# USB-PD-PSU.net
KiCad netlist of a schematic drawn in EAGLE
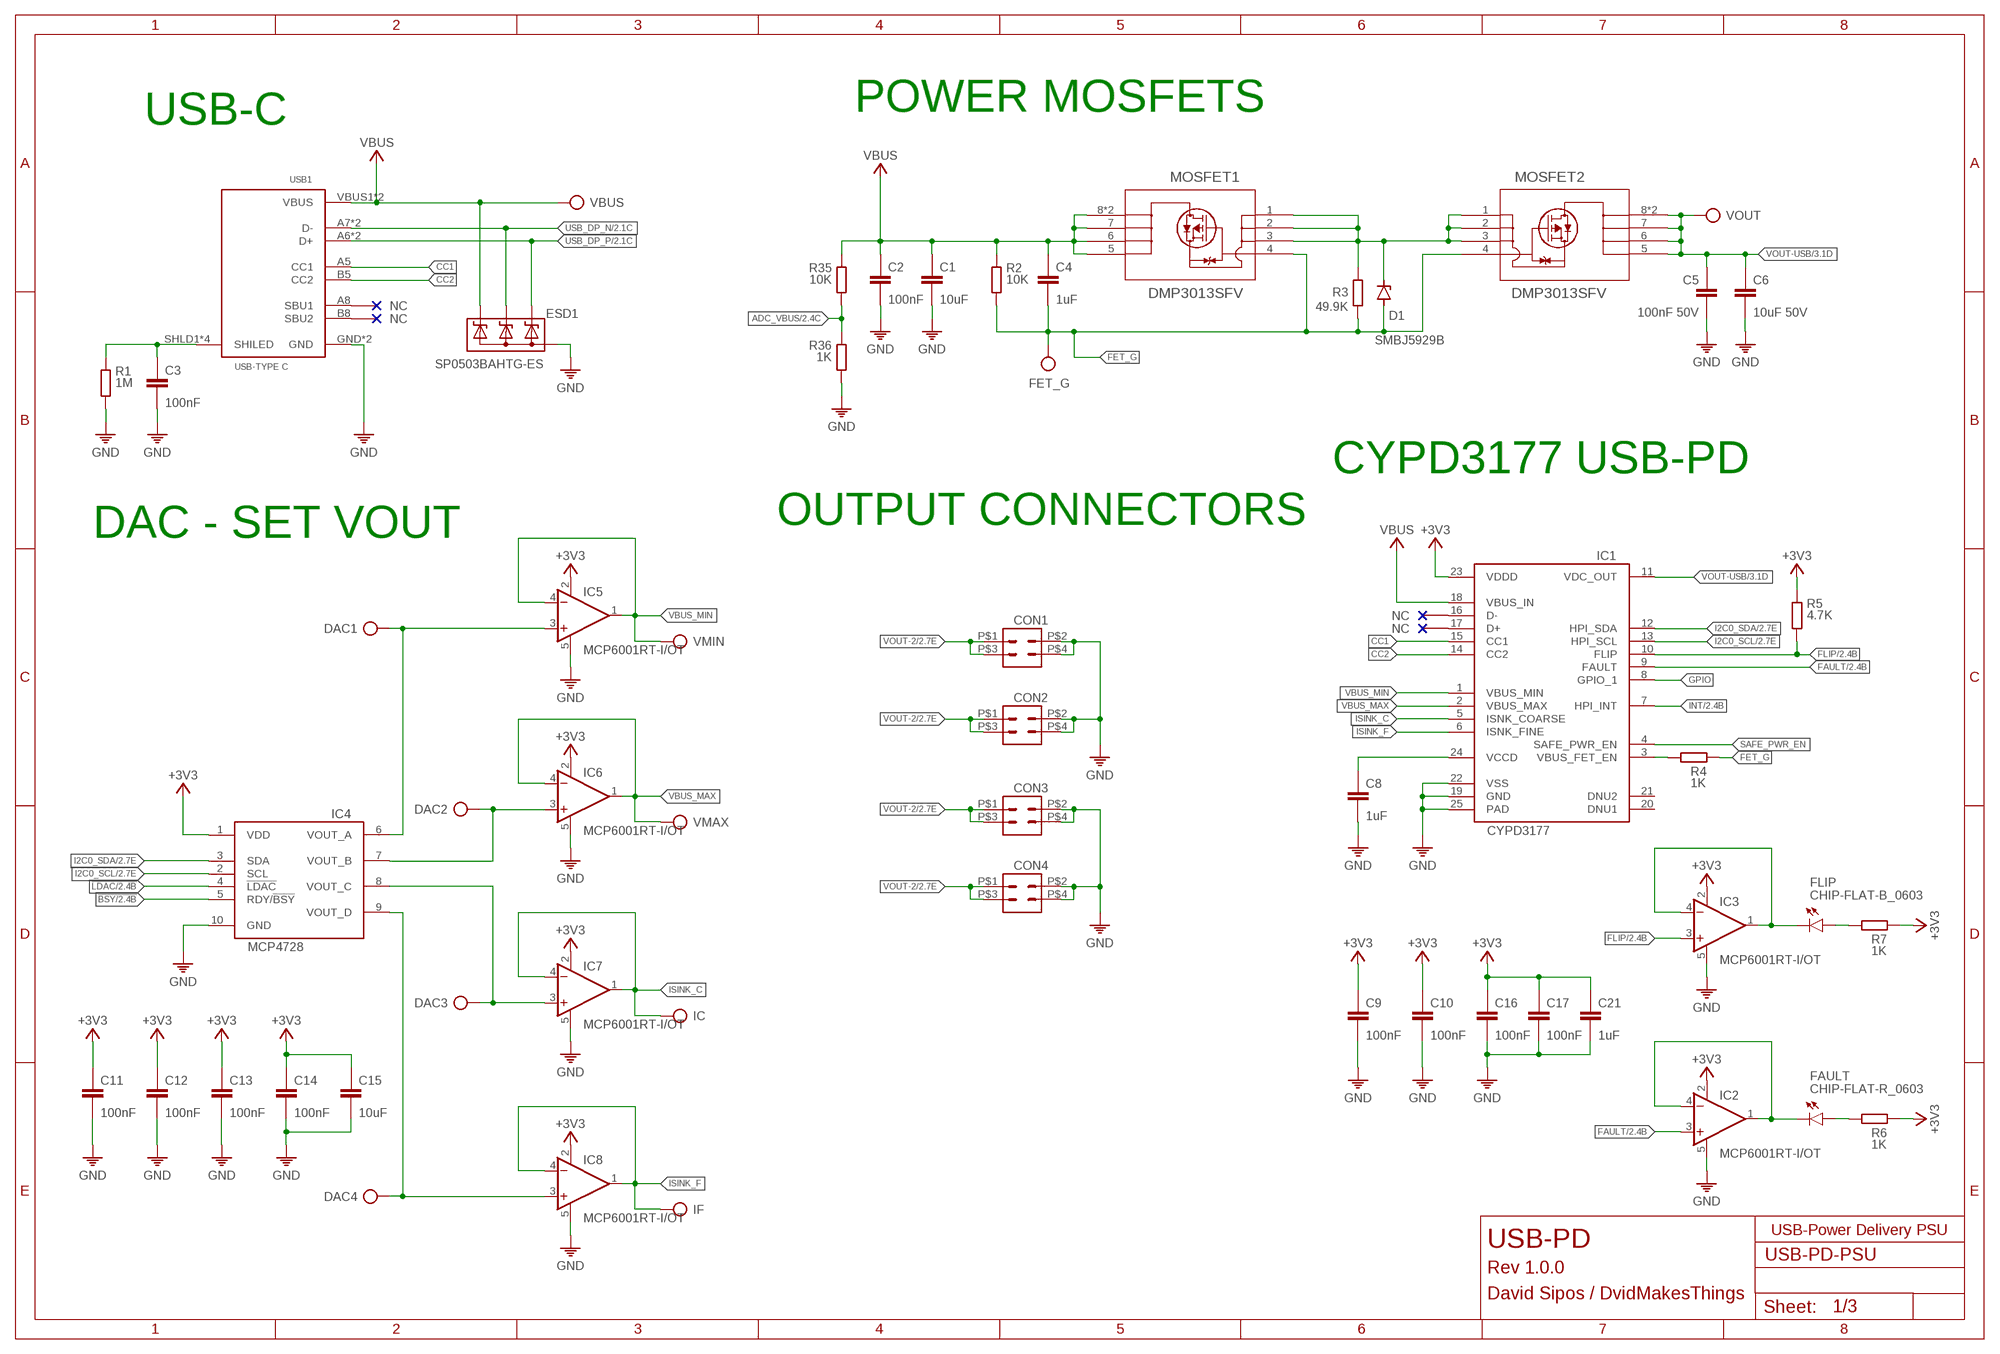
[diagram p0: schematic, sheet 1]
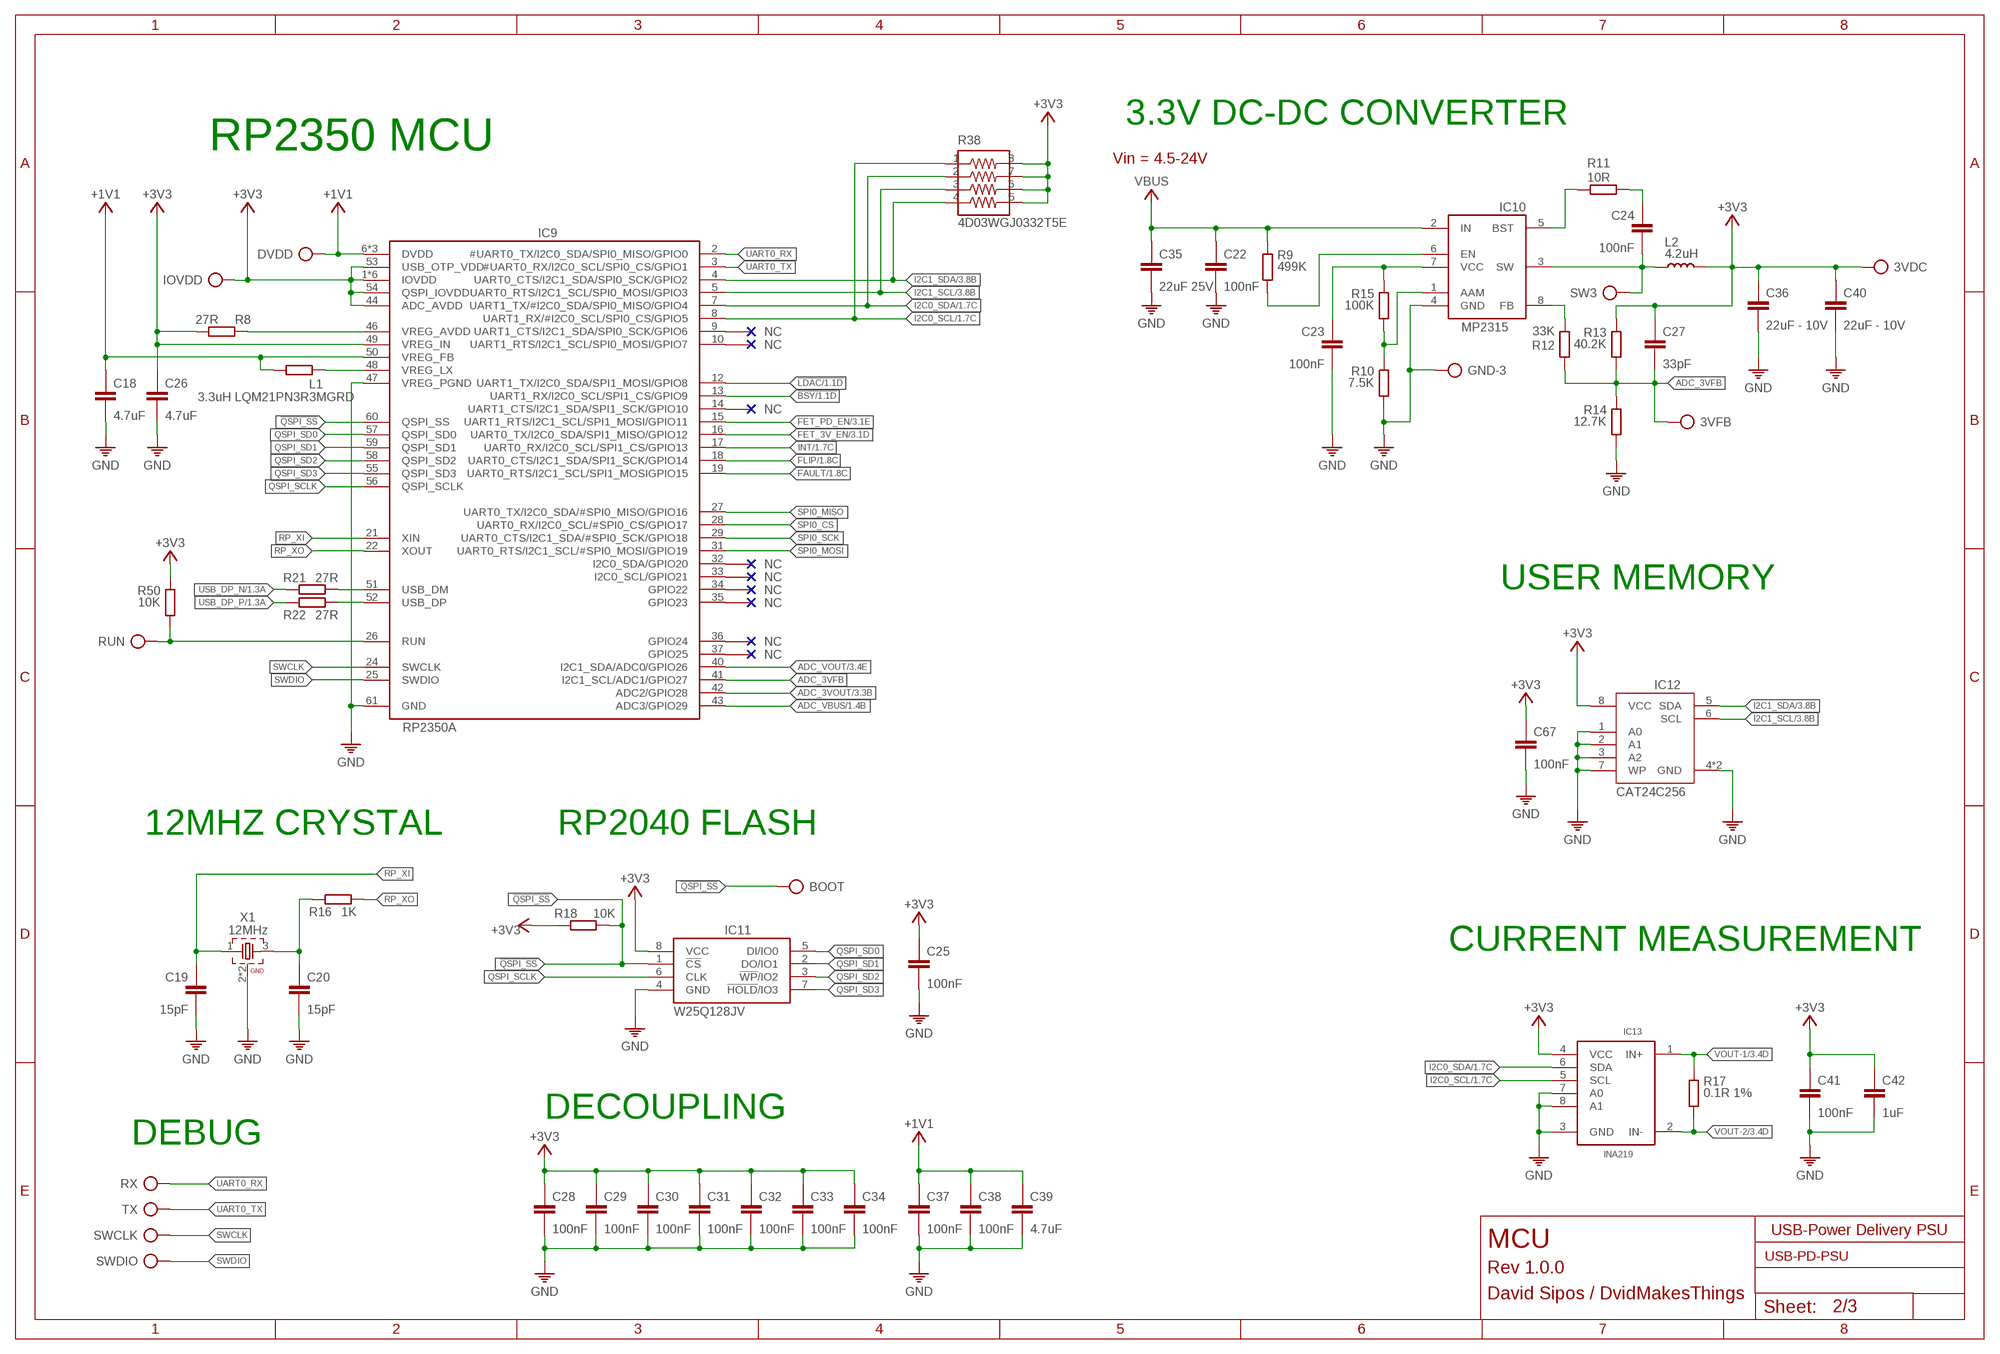
[diagram p1: schematic, sheet 2]
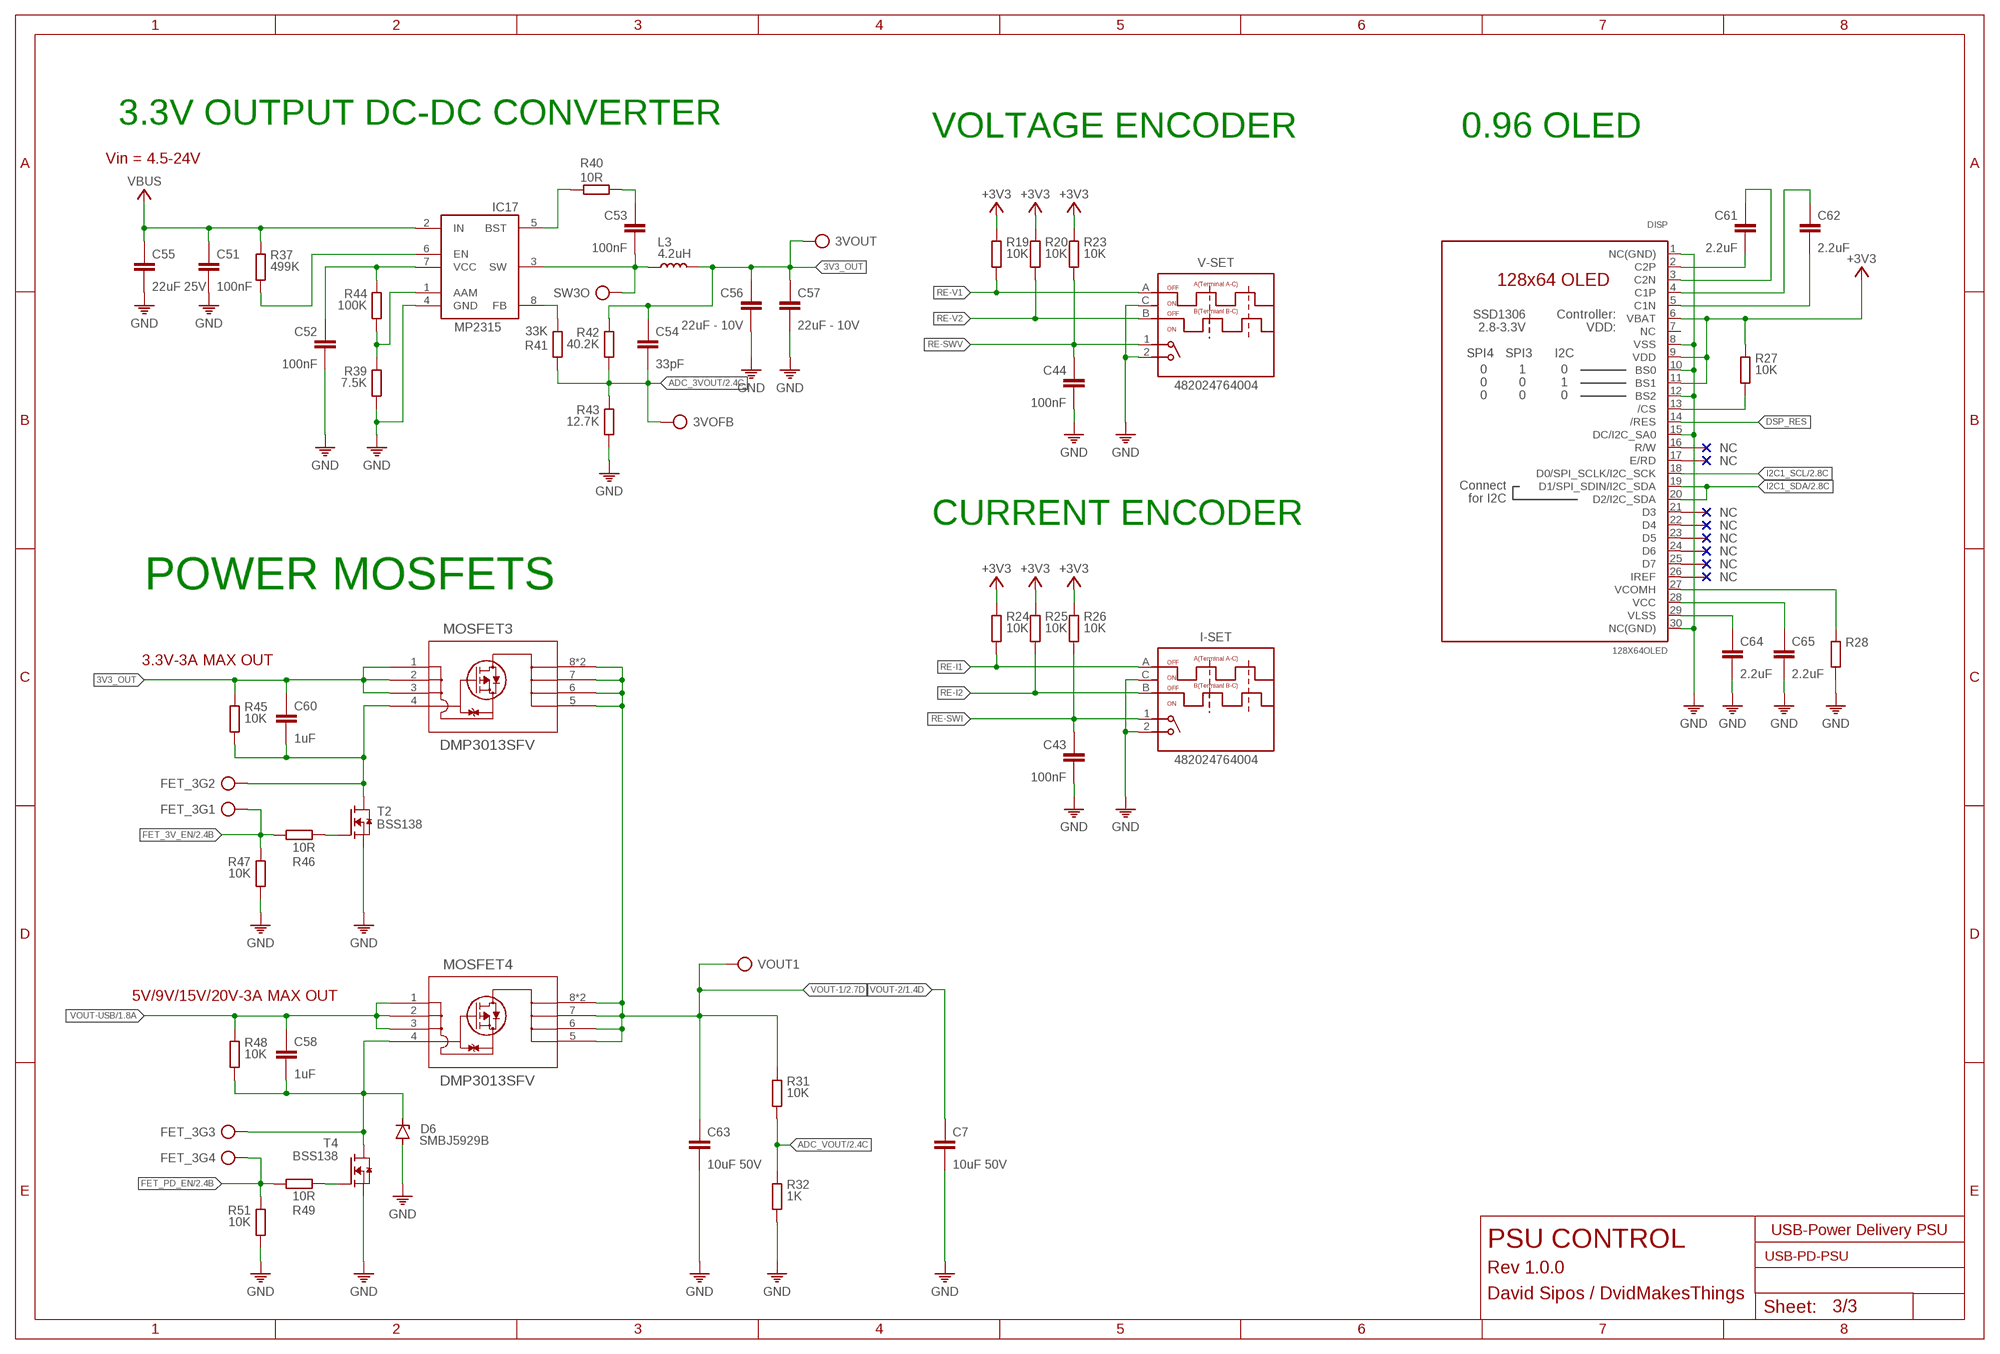
[diagram p2: schematic, sheet 3]

(export (version "E")
  (design (tool "Eeschema 10.0.6"))
  (components
    (comp (ref "C1")
      (value "10uF")
      (footprint "eagle-import:C0805")
      (libsource (lib "eagle-import") (part "C-0805"))
    )
    (comp (ref "C2")
      (value "100nF")
      (footprint "eagle-import:C0603")
      (libsource (lib "eagle-import") (part "C-0603"))
    )
    (comp (ref "C3")
      (value "100nF")
      (footprint "eagle-import:C0603")
      (libsource (lib "eagle-import") (part "C-0603"))
    )
    (comp (ref "C4")
      (value "1uF")
      (footprint "eagle-import:C0603")
      (libsource (lib "eagle-import") (part "C-0603"))
    )
    (comp (ref "C5")
      (value "100nF 50V")
      (footprint "eagle-import:C0603")
      (libsource (lib "eagle-import") (part "C-0603"))
    )
    (comp (ref "C6")
      (value "10uF 50V")
      (footprint "eagle-import:C0603")
      (libsource (lib "eagle-import") (part "C-0603"))
    )
    (comp (ref "C8")
      (value "1uF")
      (footprint "eagle-import:0201")
      (libsource (lib "eagle-import") (part "C-0201"))
    )
    (comp (ref "C9")
      (value "100nF")
      (footprint "eagle-import:0201")
      (libsource (lib "eagle-import") (part "C-0201"))
    )
    (comp (ref "C10")
      (value "100nF")
      (footprint "eagle-import:0201")
      (libsource (lib "eagle-import") (part "C-0201"))
    )
    (comp (ref "C11")
      (value "100nF")
      (footprint "eagle-import:0201")
      (libsource (lib "eagle-import") (part "C-0201"))
    )
    (comp (ref "C12")
      (value "100nF")
      (footprint "eagle-import:0201")
      (libsource (lib "eagle-import") (part "C-0201"))
    )
    (comp (ref "C13")
      (value "100nF")
      (footprint "eagle-import:0201")
      (libsource (lib "eagle-import") (part "C-0201"))
    )
    (comp (ref "C14")
      (value "100nF")
      (footprint "eagle-import:0201")
      (libsource (lib "eagle-import") (part "C-0201"))
    )
    (comp (ref "C15")
      (value "10uF")
      (footprint "eagle-import:0201")
      (libsource (lib "eagle-import") (part "C-0201"))
    )
    (comp (ref "C16")
      (value "100nF")
      (footprint "eagle-import:0201")
      (libsource (lib "eagle-import") (part "C-0201"))
    )
    (comp (ref "C17")
      (value "100nF")
      (footprint "eagle-import:0201")
      (libsource (lib "eagle-import") (part "C-0201"))
    )
    (comp (ref "C21")
      (value "1uF")
      (footprint "eagle-import:0201")
      (libsource (lib "eagle-import") (part "C-0201"))
    )
    (comp (ref "CON1")
      (value "CON-2X2SMD")
      (footprint "eagle-import:2X2_SMD")
      (libsource (lib "eagle-import") (part "CON-2X2SMD"))
    )
    (comp (ref "CON2")
      (value "CON-2X2SMD")
      (footprint "eagle-import:2X2_SMD")
      (libsource (lib "eagle-import") (part "CON-2X2SMD"))
    )
    (comp (ref "CON3")
      (value "CON-2X2SMD")
      (footprint "eagle-import:2X2_SMD")
      (libsource (lib "eagle-import") (part "CON-2X2SMD"))
    )
    (comp (ref "CON4")
      (value "CON-2X2SMD")
      (footprint "eagle-import:2X2_SMD")
      (libsource (lib "eagle-import") (part "CON-2X2SMD"))
    )
    (comp (ref "D1")
      (value "SMBJ5929B")
      (footprint "eagle-import:DIOM5226X290N")
      (libsource (lib "eagle-import") (part "ZENERDO-214AC(SMA)"))
    )
    (comp (ref "DAC1")
      (value "TP")
      (footprint "eagle-import:TP")
      (libsource (lib "eagle-import") (part "TP"))
    )
    (comp (ref "DAC2")
      (value "TP")
      (footprint "eagle-import:TP")
      (libsource (lib "eagle-import") (part "TP"))
    )
    (comp (ref "DAC3")
      (value "TP")
      (footprint "eagle-import:TP")
      (libsource (lib "eagle-import") (part "TP"))
    )
    (comp (ref "DAC4")
      (value "TP")
      (footprint "eagle-import:TP")
      (libsource (lib "eagle-import") (part "TP"))
    )
    (comp (ref "ESD1")
      (value "SP0503BAHTG-ES")
      (footprint "eagle-import:SOT143")
      (libsource (lib "eagle-import") (part "SP0503BAHT"))
    )
    (comp (ref "FAULT")
      (value "CHIP-FLAT-R_0603")
      (footprint "eagle-import:LEDC1608X55N_FLAT-R")
      (libsource (lib "eagle-import") (part "CHIP-FLAT-R_0603-0.55MM"))
    )
    (comp (ref "FET_G")
      (value "TP")
      (footprint "eagle-import:TP")
      (libsource (lib "eagle-import") (part "TP"))
    )
    (comp (ref "FLIP")
      (value "CHIP-FLAT-B_0603")
      (footprint "eagle-import:LEDC1608X55N_FLAT-B")
      (libsource (lib "eagle-import") (part "CHIP-FLAT-B_0603-0.55MM"))
    )
    (comp (ref "IC") (value "TP") (footprint "eagle-import:TP") (libsource (lib "eagle-import") (part "TP")))
    (comp (ref "IC1")
      (value "CYPD3177")
      (footprint "eagle-import:QFN24")
      (libsource (lib "eagle-import") (part "CYPD3177-24LQXQT"))
    )
    (comp (ref "IC2")
      (value "MCP6001RT-I/OT")
      (footprint "eagle-import:SOT23-5")
      (libsource (lib "eagle-import") (part "MCP6001RT"))
    )
    (comp (ref "IC3")
      (value "MCP6001RT-I/OT")
      (footprint "eagle-import:SOT23-5")
      (libsource (lib "eagle-import") (part "MCP6001RT"))
    )
    (comp (ref "IC4")
      (value "MCP4728")
      (footprint "eagle-import:MSOP10")
      (libsource (lib "eagle-import") (part "MCP4728"))
    )
    (comp (ref "IC5")
      (value "MCP6001RT-I/OT")
      (footprint "eagle-import:SOT23-5")
      (libsource (lib "eagle-import") (part "MCP6001RT"))
    )
    (comp (ref "IC6")
      (value "MCP6001RT-I/OT")
      (footprint "eagle-import:SOT23-5")
      (libsource (lib "eagle-import") (part "MCP6001RT"))
    )
    (comp (ref "IC7")
      (value "MCP6001RT-I/OT")
      (footprint "eagle-import:SOT23-5")
      (libsource (lib "eagle-import") (part "MCP6001RT"))
    )
    (comp (ref "IC8")
      (value "MCP6001RT-I/OT")
      (footprint "eagle-import:SOT23-5")
      (libsource (lib "eagle-import") (part "MCP6001RT"))
    )
    (comp (ref "IF") (value "TP") (footprint "eagle-import:TP") (libsource (lib "eagle-import") (part "TP")))
    (comp (ref "MOSFET1")
      (value "DMP3013SFV")
      (footprint "eagle-import:POWERDI3333-8_UX_DIO-L")
      (fields
        (field (name "MANUFACTURER_PART_NUMBER") "DMP3013SFV-7")
        (field (name "COPYRIGHT") "Copyright (C) 2025 Ultra Librarian. All rights reserved.")
      )
      (libsource (lib "eagle-import") (part "DMP3013SFV-7POWERDI3333-8_UX_DIO"))
    )
    (comp (ref "MOSFET2")
      (value "DMP3013SFV")
      (footprint "eagle-import:POWERDI3333-8_UX_DIO-L")
      (fields
        (field (name "MANUFACTURER_PART_NUMBER") "DMP3013SFV-7")
        (field (name "COPYRIGHT") "Copyright (C) 2025 Ultra Librarian. All rights reserved.")
      )
      (libsource (lib "eagle-import") (part "DMP3013SFV-7POWERDI3333-8_UX_DIO"))
    )
    (comp (ref "R1")
      (value "1M")
      (footprint "eagle-import:0402")
      (libsource (lib "eagle-import") (part "R0402"))
    )
    (comp (ref "R2")
      (value "10K")
      (footprint "eagle-import:0402")
      (libsource (lib "eagle-import") (part "R0402"))
    )
    (comp (ref "R3")
      (value "49.9K")
      (footprint "eagle-import:0402")
      (libsource (lib "eagle-import") (part "R0402"))
    )
    (comp (ref "R4")
      (value "1K")
      (footprint "eagle-import:R0201")
      (libsource (lib "eagle-import") (part "R0201"))
    )
    (comp (ref "R5")
      (value "4.7K")
      (footprint "eagle-import:R0201")
      (libsource (lib "eagle-import") (part "R0201"))
    )
    (comp (ref "R6")
      (value "1K")
      (footprint "eagle-import:R0201")
      (libsource (lib "eagle-import") (part "R0201"))
    )
    (comp (ref "R7")
      (value "1K")
      (footprint "eagle-import:R0201")
      (libsource (lib "eagle-import") (part "R0201"))
    )
    (comp (ref "R35")
      (value "10K")
      (footprint "eagle-import:0402")
      (libsource (lib "eagle-import") (part "R0402"))
    )
    (comp (ref "R36")
      (value "1K")
      (footprint "eagle-import:0402")
      (libsource (lib "eagle-import") (part "R0402"))
    )
    (comp (ref "USB1")
      (value "USB_C-THT")
      (footprint "eagle-import:USB-C")
      (libsource (lib "eagle-import") (part "USB_C-THT"))
    )
    (comp (ref "VBUS")
      (value "TP")
      (footprint "eagle-import:TP")
      (libsource (lib "eagle-import") (part "TP"))
    )
    (comp (ref "VMAX")
      (value "TP")
      (footprint "eagle-import:TP")
      (libsource (lib "eagle-import") (part "TP"))
    )
    (comp (ref "VMIN")
      (value "TP")
      (footprint "eagle-import:TP")
      (libsource (lib "eagle-import") (part "TP"))
    )
    (comp (ref "VOUT")
      (value "TP")
      (footprint "eagle-import:TP")
      (libsource (lib "eagle-import") (part "TP"))
    )
    (comp (ref "3VDC")
      (value "TP")
      (footprint "eagle-import:TP")
      (libsource (lib "eagle-import") (part "TP"))
    )
    (comp (ref "3VFB")
      (value "TP")
      (footprint "eagle-import:TP")
      (libsource (lib "eagle-import") (part "TP"))
    )
    (comp (ref "BOOT")
      (value "TP")
      (footprint "eagle-import:TP")
      (libsource (lib "eagle-import") (part "TP"))
    )
    (comp (ref "C18")
      (value "4.7uF")
      (footprint "eagle-import:0201")
      (libsource (lib "eagle-import") (part "C-0201"))
    )
    (comp (ref "C19")
      (value "15pF")
      (footprint "eagle-import:C0402")
      (libsource (lib "eagle-import") (part "C-0402"))
    )
    (comp (ref "C20")
      (value "15pF")
      (footprint "eagle-import:C0402")
      (libsource (lib "eagle-import") (part "C-0402"))
    )
    (comp (ref "C22")
      (value "100nF")
      (footprint "eagle-import:0402")
      (libsource (lib "eagle-import") (part "C0402"))
    )
    (comp (ref "C23")
      (value "100nF")
      (footprint "eagle-import:0402")
      (libsource (lib "eagle-import") (part "C0402"))
    )
    (comp (ref "C24")
      (value "100nF")
      (footprint "eagle-import:0402")
      (libsource (lib "eagle-import") (part "C0402"))
    )
    (comp (ref "C25")
      (value "100nF")
      (footprint "eagle-import:C0402")
      (libsource (lib "eagle-import") (part "C-0402"))
    )
    (comp (ref "C26")
      (value "4.7uF")
      (footprint "eagle-import:0201")
      (libsource (lib "eagle-import") (part "C-0201"))
    )
    (comp (ref "C27")
      (value "33pF")
      (footprint "eagle-import:0402")
      (libsource (lib "eagle-import") (part "C0402"))
    )
    (comp (ref "C28")
      (value "100nF")
      (footprint "eagle-import:0201")
      (libsource (lib "eagle-import") (part "C-0201"))
    )
    (comp (ref "C29")
      (value "100nF")
      (footprint "eagle-import:0201")
      (libsource (lib "eagle-import") (part "C-0201"))
    )
    (comp (ref "C30")
      (value "100nF")
      (footprint "eagle-import:0201")
      (libsource (lib "eagle-import") (part "C-0201"))
    )
    (comp (ref "C31")
      (value "100nF")
      (footprint "eagle-import:0201")
      (libsource (lib "eagle-import") (part "C-0201"))
    )
    (comp (ref "C32")
      (value "100nF")
      (footprint "eagle-import:0201")
      (libsource (lib "eagle-import") (part "C-0201"))
    )
    (comp (ref "C33")
      (value "100nF")
      (footprint "eagle-import:0201")
      (libsource (lib "eagle-import") (part "C-0201"))
    )
    (comp (ref "C34")
      (value "100nF")
      (footprint "eagle-import:0201")
      (libsource (lib "eagle-import") (part "C-0201"))
    )
    (comp (ref "C35")
      (value "22uF 25V")
      (footprint "eagle-import:C1206")
      (libsource (lib "eagle-import") (part "C-1206"))
    )
    (comp (ref "C36")
      (value "22uF - 10V")
      (footprint "eagle-import:C1206")
      (libsource (lib "eagle-import") (part "C-1206"))
    )
    (comp (ref "C37")
      (value "100nF")
      (footprint "eagle-import:0201")
      (libsource (lib "eagle-import") (part "C-0201"))
    )
    (comp (ref "C38")
      (value "100nF")
      (footprint "eagle-import:0201")
      (libsource (lib "eagle-import") (part "C-0201"))
    )
    (comp (ref "C39")
      (value "4.7uF")
      (footprint "eagle-import:0201")
      (libsource (lib "eagle-import") (part "C-0201"))
    )
    (comp (ref "C40")
      (value "22uF - 10V")
      (footprint "eagle-import:C1206")
      (libsource (lib "eagle-import") (part "C-1206"))
    )
    (comp (ref "C41")
      (value "100nF")
      (footprint "eagle-import:0201")
      (libsource (lib "eagle-import") (part "C-0201"))
    )
    (comp (ref "C42")
      (value "1uF")
      (footprint "eagle-import:0201")
      (libsource (lib "eagle-import") (part "C-0201"))
    )
    (comp (ref "C67")
      (value "100nF")
      (footprint "eagle-import:0201")
      (libsource (lib "eagle-import") (part "C-0201"))
    )
    (comp (ref "DVDD")
      (value "TP")
      (footprint "eagle-import:TP")
      (libsource (lib "eagle-import") (part "TP"))
    )
    (comp (ref "GND-3")
      (value "TP")
      (footprint "eagle-import:TP")
      (libsource (lib "eagle-import") (part "TP"))
    )
    (comp (ref "IC9")
      (value "RP2350AA")
      (footprint "eagle-import:QFN40P700X700X85-61T340N")
      (libsource (lib "eagle-import") (part "RP2350AA"))
    )
    (comp (ref "IC10")
      (value "MP2315S")
      (footprint "eagle-import:SOT65P280X110-8N")
      (libsource (lib "eagle-import") (part "MP2315TSOT23-8"))
    )
    (comp (ref "IC11")
      (value "W25Q128JVPIQ")
      (footprint "eagle-import:SON127P600X500X75-8N")
      (libsource (lib "eagle-import") (part "W25Q128JVP"))
    )
    (comp (ref "IC12")
      (value "CAT24C512HU5IGT3")
      (footprint "eagle-import:SON50P300X200X50-9T130X140N")
      (libsource (lib "eagle-import") (part "CAT24C256-HU4"))
    )
    (comp (ref "IC13")
      (value "INA219BIDCNT")
      (footprint "eagle-import:SOT23-8")
      (libsource (lib "eagle-import") (part "INA219BIDCNT"))
    )
    (comp (ref "IOVDD")
      (value "TP")
      (footprint "eagle-import:TP")
      (libsource (lib "eagle-import") (part "TP"))
    )
    (comp (ref "L1")
      (value "3.3uH LQM21PN3R3MGRD")
      (footprint "eagle-import:0805")
      (libsource (lib "eagle-import") (part "R0805"))
    )
    (comp (ref "L2")
      (value "4.2uH")
      (footprint "eagle-import:SRR5228A")
      (libsource (lib "eagle-import") (part "L"))
    )
    (comp (ref "R8")
      (value "27R")
      (footprint "eagle-import:R0201")
      (libsource (lib "eagle-import") (part "R0201"))
    )
    (comp (ref "R9")
      (value "499K")
      (footprint "eagle-import:0402")
      (libsource (lib "eagle-import") (part "R0402"))
    )
    (comp (ref "R10")
      (value "7.5K")
      (footprint "eagle-import:0402")
      (libsource (lib "eagle-import") (part "R0402"))
    )
    (comp (ref "R11")
      (value "10R")
      (footprint "eagle-import:0402")
      (libsource (lib "eagle-import") (part "R0402"))
    )
    (comp (ref "R12")
      (value "33K")
      (footprint "eagle-import:0402")
      (libsource (lib "eagle-import") (part "R0402"))
    )
    (comp (ref "R13")
      (value "40.2K")
      (footprint "eagle-import:0402")
      (libsource (lib "eagle-import") (part "R0402"))
    )
    (comp (ref "R14")
      (value "12.7K")
      (footprint "eagle-import:0402")
      (libsource (lib "eagle-import") (part "R0402"))
    )
    (comp (ref "R15")
      (value "100K")
      (footprint "eagle-import:0402")
      (libsource (lib "eagle-import") (part "R0402"))
    )
    (comp (ref "R16")
      (value "1K")
      (footprint "eagle-import:R0201")
      (libsource (lib "eagle-import") (part "R0201"))
    )
    (comp (ref "R17")
      (value "0.1R 1%")
      (footprint "eagle-import:2512")
      (libsource (lib "eagle-import") (part "R2512"))
    )
    (comp (ref "R18")
      (value "10K")
      (footprint "eagle-import:0402")
      (libsource (lib "eagle-import") (part "R0402"))
    )
    (comp (ref "R21")
      (value "27R")
      (footprint "eagle-import:R0201")
      (libsource (lib "eagle-import") (part "R0201"))
    )
    (comp (ref "R22")
      (value "27R")
      (footprint "eagle-import:R0201")
      (libsource (lib "eagle-import") (part "R0201"))
    )
    (comp (ref "R38")
      (value "4D03WGJ0332T5E")
      (footprint "eagle-import:742C083103JP")
      (fields
        (field (name "MANUFACTURER") "CTS Resistor Products")
        (field (name "MPN") "742C083103JP")
        (field (name "CREATED_BY") "PCBLayout.com")
      )
      (libsource (lib "eagle-import") (part "742C083103JP"))
    )
    (comp (ref "R50")
      (value "10K")
      (footprint "eagle-import:0402")
      (libsource (lib "eagle-import") (part "ds_passive_46685041_R0402"))
    )
    (comp (ref "RUN") (value "TP") (footprint "eagle-import:TP") (libsource (lib "eagle-import") (part "TP")))
    (comp (ref "RX") (value "TP") (footprint "eagle-import:TP") (libsource (lib "eagle-import") (part "TP")))
    (comp (ref "SW3") (value "TP") (footprint "eagle-import:TP") (libsource (lib "eagle-import") (part "TP")))
    (comp (ref "SWCLK")
      (value "TP")
      (footprint "eagle-import:TP")
      (libsource (lib "eagle-import") (part "TP"))
    )
    (comp (ref "SWDIO")
      (value "TP")
      (footprint "eagle-import:TP")
      (libsource (lib "eagle-import") (part "TP"))
    )
    (comp (ref "TX") (value "TP") (footprint "eagle-import:TP") (libsource (lib "eagle-import") (part "TP")))
    (comp (ref "X1")
      (value "12MHz")
      (footprint "eagle-import:WE-XTAL_CFPX-180")
      (fields (field (name "TOLERANCE") "±20ppm"))
      (libsource (lib "eagle-import") (part "WE-XTAL_CFPX-180_830055295"))
    )
    (comp (ref "3VOFB")
      (value "TP")
      (footprint "eagle-import:TP")
      (libsource (lib "eagle-import") (part "TP"))
    )
    (comp (ref "3VOUT")
      (value "TP")
      (footprint "eagle-import:TP")
      (libsource (lib "eagle-import") (part "TP"))
    )
    (comp (ref "C7")
      (value "10uF 50V")
      (footprint "eagle-import:C0805")
      (libsource (lib "eagle-import") (part "C-0805"))
    )
    (comp (ref "C43")
      (value "100nF")
      (footprint "eagle-import:0201")
      (libsource (lib "eagle-import") (part "C-0201"))
    )
    (comp (ref "C44")
      (value "100nF")
      (footprint "eagle-import:0201")
      (libsource (lib "eagle-import") (part "C-0201"))
    )
    (comp (ref "C51")
      (value "100nF")
      (footprint "eagle-import:0402")
      (libsource (lib "eagle-import") (part "C0402"))
    )
    (comp (ref "C52")
      (value "100nF")
      (footprint "eagle-import:0402")
      (libsource (lib "eagle-import") (part "C0402"))
    )
    (comp (ref "C53")
      (value "100nF")
      (footprint "eagle-import:0402")
      (libsource (lib "eagle-import") (part "C0402"))
    )
    (comp (ref "C54")
      (value "33pF")
      (footprint "eagle-import:0402")
      (libsource (lib "eagle-import") (part "C0402"))
    )
    (comp (ref "C55")
      (value "22uF 25V")
      (footprint "eagle-import:C1206")
      (libsource (lib "eagle-import") (part "C-1206"))
    )
    (comp (ref "C56")
      (value "22uF - 10V")
      (footprint "eagle-import:C1206")
      (libsource (lib "eagle-import") (part "C-1206"))
    )
    (comp (ref "C57")
      (value "22uF - 10V")
      (footprint "eagle-import:C1206")
      (libsource (lib "eagle-import") (part "C-1206"))
    )
    (comp (ref "C58")
      (value "1uF")
      (footprint "eagle-import:C0603")
      (libsource (lib "eagle-import") (part "C-0603"))
    )
    (comp (ref "C60")
      (value "1uF")
      (footprint "eagle-import:C0603")
      (libsource (lib "eagle-import") (part "C-0603"))
    )
    (comp (ref "C61")
      (value "2.2uF")
      (footprint "eagle-import:0201")
      (libsource (lib "eagle-import") (part "C-0201"))
    )
    (comp (ref "C62")
      (value "2.2uF")
      (footprint "eagle-import:0201")
      (libsource (lib "eagle-import") (part "C-0201"))
    )
    (comp (ref "C63")
      (value "10uF 50V")
      (footprint "eagle-import:C0603")
      (libsource (lib "eagle-import") (part "C-0603"))
    )
    (comp (ref "C64")
      (value "2.2uF")
      (footprint "eagle-import:0201")
      (libsource (lib "eagle-import") (part "C-0201"))
    )
    (comp (ref "C65")
      (value "2.2uF")
      (footprint "eagle-import:0201")
      (libsource (lib "eagle-import") (part "C-0201"))
    )
    (comp (ref "D6")
      (value "SMBJ5929B")
      (footprint "eagle-import:DIOM5226X290N")
      (libsource (lib "eagle-import") (part "ZENERDO-214AC(SMA)"))
    )
    (comp (ref "DISP")
      (value "128X64OLED")
      (footprint "eagle-import:UG2864")
      (libsource (lib "eagle-import") (part "128X64OLED"))
    )
    (comp (ref "FET_3G1")
      (value "TP")
      (footprint "eagle-import:TP")
      (libsource (lib "eagle-import") (part "TP"))
    )
    (comp (ref "FET_3G2")
      (value "TP")
      (footprint "eagle-import:TP")
      (libsource (lib "eagle-import") (part "TP"))
    )
    (comp (ref "FET_3G3")
      (value "TP")
      (footprint "eagle-import:TP")
      (libsource (lib "eagle-import") (part "TP"))
    )
    (comp (ref "FET_3G4")
      (value "TP")
      (footprint "eagle-import:TP")
      (libsource (lib "eagle-import") (part "TP"))
    )
    (comp (ref "I-SET")
      (value "482024764004")
      (footprint "eagle-import:WS-ENTV_482024764004")
      (libsource (lib "eagle-import") (part "482024764004"))
    )
    (comp (ref "IC17")
      (value "MP2315S")
      (footprint "eagle-import:SOT65P280X110-8N")
      (libsource (lib "eagle-import") (part "MP2315TSOT23-8"))
    )
    (comp (ref "L3")
      (value "4.2uH")
      (footprint "eagle-import:SRR5228A")
      (libsource (lib "eagle-import") (part "L"))
    )
    (comp (ref "MOSFET3")
      (value "DMP3013SFV")
      (footprint "eagle-import:POWERDI3333-8_UX_DIO-L")
      (fields
        (field (name "MANUFACTURER_PART_NUMBER") "DMP3013SFV-7")
        (field (name "COPYRIGHT") "Copyright (C) 2025 Ultra Librarian. All rights reserved.")
      )
      (libsource (lib "eagle-import") (part "DMP3013SFV-7POWERDI3333-8_UX_DIO"))
    )
    (comp (ref "MOSFET4")
      (value "DMP3013SFV")
      (footprint "eagle-import:POWERDI3333-8_UX_DIO-L")
      (fields
        (field (name "MANUFACTURER_PART_NUMBER") "DMP3013SFV-7")
        (field (name "COPYRIGHT") "Copyright (C) 2025 Ultra Librarian. All rights reserved.")
      )
      (libsource (lib "eagle-import") (part "DMP3013SFV-7POWERDI3333-8_UX_DIO"))
    )
    (comp (ref "R19")
      (value "10K")
      (footprint "eagle-import:R0201")
      (libsource (lib "eagle-import") (part "R0201"))
    )
    (comp (ref "R20")
      (value "10K")
      (footprint "eagle-import:R0201")
      (libsource (lib "eagle-import") (part "R0201"))
    )
    (comp (ref "R23")
      (value "10K")
      (footprint "eagle-import:R0201")
      (libsource (lib "eagle-import") (part "R0201"))
    )
    (comp (ref "R24")
      (value "10K")
      (footprint "eagle-import:R0201")
      (libsource (lib "eagle-import") (part "R0201"))
    )
    (comp (ref "R25")
      (value "10K")
      (footprint "eagle-import:R0201")
      (libsource (lib "eagle-import") (part "R0201"))
    )
    (comp (ref "R26")
      (value "10K")
      (footprint "eagle-import:R0201")
      (libsource (lib "eagle-import") (part "R0201"))
    )
    (comp (ref "R27")
      (value "10K")
      (footprint "eagle-import:R0201")
      (libsource (lib "eagle-import") (part "R0201"))
    )
    (comp (ref "R28")
      (value "R0201")
      (footprint "eagle-import:R0201")
      (libsource (lib "eagle-import") (part "R0201"))
    )
    (comp (ref "R31")
      (value "10K")
      (footprint "eagle-import:0402")
      (libsource (lib "eagle-import") (part "R0402"))
    )
    (comp (ref "R32")
      (value "1K")
      (footprint "eagle-import:0402")
      (libsource (lib "eagle-import") (part "R0402"))
    )
    (comp (ref "R37")
      (value "499K")
      (footprint "eagle-import:0402")
      (libsource (lib "eagle-import") (part "R0402"))
    )
    (comp (ref "R39")
      (value "7.5K")
      (footprint "eagle-import:0402")
      (libsource (lib "eagle-import") (part "R0402"))
    )
    (comp (ref "R40")
      (value "10R")
      (footprint "eagle-import:0402")
      (libsource (lib "eagle-import") (part "R0402"))
    )
    (comp (ref "R41")
      (value "33K")
      (footprint "eagle-import:0402")
      (libsource (lib "eagle-import") (part "R0402"))
    )
    (comp (ref "R42")
      (value "40.2K")
      (footprint "eagle-import:0402")
      (libsource (lib "eagle-import") (part "R0402"))
    )
    (comp (ref "R43")
      (value "12.7K")
      (footprint "eagle-import:0402")
      (libsource (lib "eagle-import") (part "R0402"))
    )
    (comp (ref "R44")
      (value "100K")
      (footprint "eagle-import:0402")
      (libsource (lib "eagle-import") (part "R0402"))
    )
    (comp (ref "R45")
      (value "10K")
      (footprint "eagle-import:0402")
      (libsource (lib "eagle-import") (part "R0402"))
    )
    (comp (ref "R46")
      (value "10R")
      (footprint "eagle-import:0402")
      (libsource (lib "eagle-import") (part "R0402"))
    )
    (comp (ref "R47")
      (value "10K")
      (footprint "eagle-import:0402")
      (libsource (lib "eagle-import") (part "R0402"))
    )
    (comp (ref "R48")
      (value "10K")
      (footprint "eagle-import:0402")
      (libsource (lib "eagle-import") (part "R0402"))
    )
    (comp (ref "R49")
      (value "10R")
      (footprint "eagle-import:0402")
      (libsource (lib "eagle-import") (part "R0402"))
    )
    (comp (ref "R51")
      (value "10K")
      (footprint "eagle-import:0402")
      (libsource (lib "eagle-import") (part "R0402"))
    )
    (comp (ref "SW3O")
      (value "TP")
      (footprint "eagle-import:TP")
      (libsource (lib "eagle-import") (part "TP"))
    )
    (comp (ref "T2")
      (value "BSS138")
      (footprint "eagle-import:SOT23")
      (libsource (lib "eagle-import") (part "BSS138"))
    )
    (comp (ref "T4")
      (value "BSS138")
      (footprint "eagle-import:SOT23")
      (libsource (lib "eagle-import") (part "BSS138"))
    )
    (comp (ref "V-SET")
      (value "482024764004")
      (footprint "eagle-import:WS-ENTV_482024764004")
      (libsource (lib "eagle-import") (part "482024764004"))
    )
    (comp (ref "VOUT1")
      (value "TP")
      (footprint "eagle-import:TP")
      (libsource (lib "eagle-import") (part "TP"))
    )
  )
  (nets
    (net (code "1") (name "+1V1") (class "Default")
      (node (ref "C18") (pin "1") (pinfunction "1_1") (pintype "passive"))
      (node (ref "C37") (pin "1") (pinfunction "1_1") (pintype "passive"))
      (node (ref "C38") (pin "1") (pinfunction "1_1") (pintype "passive"))
      (node (ref "C39") (pin "1") (pinfunction "1_1") (pintype "passive"))
      (node (ref "DVDD") (pin "TP") (pinfunction "P$1_TP") (pintype "bidirectional"))
      (node (ref "IC9") (pin "23") (pinfunction "DVDD_23") (pintype "power_in"))
      (node (ref "IC9") (pin "39") (pinfunction "DVDD_39") (pintype "power_in"))
      (node (ref "IC9") (pin "50") (pinfunction "VREG_FB_50") (pintype "power_in"))
      (node (ref "IC9") (pin "6") (pinfunction "DVDD_6") (pintype "power_in"))
      (node (ref "L1") (pin "2") (pinfunction "2_2") (pintype "passive"))
    )
    (net (code "2") (name "+3V3") (class "Default")
      (node (ref "3VDC") (pin "TP") (pinfunction "P$1_TP") (pintype "bidirectional"))
      (node (ref "C10") (pin "1") (pinfunction "1_1") (pintype "passive"))
      (node (ref "C11") (pin "1") (pinfunction "1_1") (pintype "passive"))
      (node (ref "C12") (pin "1") (pinfunction "1_1") (pintype "passive"))
      (node (ref "C13") (pin "1") (pinfunction "1_1") (pintype "passive"))
      (node (ref "C14") (pin "1") (pinfunction "1_1") (pintype "passive"))
      (node (ref "C15") (pin "1") (pinfunction "1_1") (pintype "passive"))
      (node (ref "C16") (pin "1") (pinfunction "1_1") (pintype "passive"))
      (node (ref "C17") (pin "1") (pinfunction "1_1") (pintype "passive"))
      (node (ref "C21") (pin "1") (pinfunction "1_1") (pintype "passive"))
      (node (ref "C25") (pin "1") (pinfunction "1_1") (pintype "passive"))
      (node (ref "C26") (pin "1") (pinfunction "1_1") (pintype "passive"))
      (node (ref "C27") (pin "1") (pinfunction "1_1") (pintype "passive"))
      (node (ref "C28") (pin "1") (pinfunction "1_1") (pintype "passive"))
      (node (ref "C29") (pin "1") (pinfunction "1_1") (pintype "passive"))
      (node (ref "C30") (pin "1") (pinfunction "1_1") (pintype "passive"))
      (node (ref "C31") (pin "1") (pinfunction "1_1") (pintype "passive"))
      (node (ref "C32") (pin "1") (pinfunction "1_1") (pintype "passive"))
      (node (ref "C33") (pin "1") (pinfunction "1_1") (pintype "passive"))
      (node (ref "C34") (pin "1") (pinfunction "1_1") (pintype "passive"))
      (node (ref "C36") (pin "1") (pinfunction "1_1") (pintype "passive"))
      (node (ref "C40") (pin "1") (pinfunction "1_1") (pintype "passive"))
      (node (ref "C41") (pin "1") (pinfunction "1_1") (pintype "passive"))
      (node (ref "C42") (pin "1") (pinfunction "1_1") (pintype "passive"))
      (node (ref "C67") (pin "1") (pinfunction "1_1") (pintype "passive"))
      (node (ref "C9") (pin "1") (pinfunction "1_1") (pintype "passive"))
      (node (ref "DISP") (pin "11") (pinfunction "BS1_11") (pintype "input"))
      (node (ref "DISP") (pin "6") (pinfunction "VBAT_6") (pintype "input"))
      (node (ref "DISP") (pin "9") (pinfunction "VDD_9") (pintype "power_in"))
      (node (ref "IC1") (pin "23") (pinfunction "VDDD_23") (pintype "power_in"))
      (node (ref "IC11") (pin "8") (pinfunction "VCC_8") (pintype "power_in"))
      (node (ref "IC12") (pin "8") (pinfunction "VCC_8") (pintype "power_in"))
      (node (ref "IC13") (pin "4") (pinfunction "VCC_4") (pintype "bidirectional"))
      (node (ref "IC2") (pin "2") (pinfunction "V+_2") (pintype "power_in"))
      (node (ref "IC3") (pin "2") (pinfunction "V+_2") (pintype "power_in"))
      (node (ref "IC4") (pin "1") (pinfunction "VDD_1") (pintype "power_in"))
      (node (ref "IC5") (pin "2") (pinfunction "V+_2") (pintype "power_in"))
      (node (ref "IC6") (pin "2") (pinfunction "V+_2") (pintype "power_in"))
      (node (ref "IC7") (pin "2") (pinfunction "V+_2") (pintype "power_in"))
      (node (ref "IC8") (pin "2") (pinfunction "V+_2") (pintype "power_in"))
      (node (ref "IC9") (pin "1") (pinfunction "IOVDD_1") (pintype "power_in"))
      (node (ref "IC9") (pin "11") (pinfunction "IOVDD_11") (pintype "power_in"))
      (node (ref "IC9") (pin "20") (pinfunction "IOVDD_20") (pintype "power_in"))
      (node (ref "IC9") (pin "30") (pinfunction "IOVDD_30") (pintype "power_in"))
      (node (ref "IC9") (pin "38") (pinfunction "IOVDD_38") (pintype "power_in"))
      (node (ref "IC9") (pin "44") (pinfunction "ADC_AVDD_44") (pintype "power_in"))
      (node (ref "IC9") (pin "45") (pinfunction "IOVDD_45") (pintype "power_in"))
      (node (ref "IC9") (pin "49") (pinfunction "VREG_IN_49") (pintype "power_in"))
      (node (ref "IC9") (pin "53") (pinfunction "USB_OTP_VDD_53") (pintype "bidirectional"))
      (node (ref "IC9") (pin "54") (pinfunction "QSPI_IOVDD_54") (pintype "power_in"))
      (node (ref "IOVDD") (pin "TP") (pinfunction "P$1_TP") (pintype "bidirectional"))
      (node (ref "L2") (pin "2") (pinfunction "2_2") (pintype "passive"))
      (node (ref "R13") (pin "1") (pinfunction "1_1") (pintype "passive"))
      (node (ref "R18") (pin "2") (pinfunction "2_2") (pintype "passive"))
      (node (ref "R19") (pin "1") (pinfunction "1_1") (pintype "passive"))
      (node (ref "R20") (pin "1") (pinfunction "1_1") (pintype "passive"))
      (node (ref "R23") (pin "1") (pinfunction "1_1") (pintype "passive"))
      (node (ref "R24") (pin "1") (pinfunction "1_1") (pintype "passive"))
      (node (ref "R25") (pin "1") (pinfunction "1_1") (pintype "passive"))
      (node (ref "R26") (pin "1") (pinfunction "1_1") (pintype "passive"))
      (node (ref "R27") (pin "1") (pinfunction "1_1") (pintype "passive"))
      (node (ref "R38") (pin "5") (pinfunction "5_5") (pintype "passive"))
      (node (ref "R38") (pin "6") (pinfunction "6_6") (pintype "passive"))
      (node (ref "R38") (pin "7") (pinfunction "7_7") (pintype "passive"))
      (node (ref "R38") (pin "8") (pinfunction "8_8") (pintype "passive"))
      (node (ref "R5") (pin "1") (pinfunction "1_1") (pintype "passive"))
      (node (ref "R50") (pin "1") (pinfunction "1_1") (pintype "passive"))
      (node (ref "R6") (pin "1") (pinfunction "1_1") (pintype "passive"))
      (node (ref "R7") (pin "1") (pinfunction "1_1") (pintype "passive"))
      (node (ref "R8") (pin "2") (pinfunction "2_2") (pintype "passive"))
    )
    (net (code "3") (name "3V3_OUT") (class "Default")
      (node (ref "3VOUT") (pin "TP") (pinfunction "P$1_TP") (pintype "bidirectional"))
      (node (ref "C54") (pin "1") (pinfunction "1_1") (pintype "passive"))
      (node (ref "C56") (pin "1") (pinfunction "1_1") (pintype "passive"))
      (node (ref "C57") (pin "1") (pinfunction "1_1") (pintype "passive"))
      (node (ref "C60") (pin "1") (pinfunction "1_1") (pintype "passive"))
      (node (ref "L3") (pin "2") (pinfunction "2_2") (pintype "passive"))
      (node (ref "MOSFET3") (pin "1") (pinfunction "S_2_1") (pintype "passive"))
      (node (ref "MOSFET3") (pin "2") (pinfunction "S_3_2") (pintype "passive"))
      (node (ref "MOSFET3") (pin "3") (pinfunction "S_3") (pintype "passive"))
      (node (ref "R42") (pin "1") (pinfunction "1_1") (pintype "passive"))
      (node (ref "R45") (pin "1") (pinfunction "1_1") (pintype "passive"))
    )
    (net (code "4") (name "ADC_3VFB") (class "Default")
      (node (ref "3VFB") (pin "TP") (pinfunction "P$1_TP") (pintype "bidirectional"))
      (node (ref "C27") (pin "2") (pinfunction "2_2") (pintype "passive"))
      (node (ref "IC9") (pin "41") (pinfunction "I2C1_SCL/ADC1/GPIO27_41") (pintype "bidirectional"))
      (node (ref "R12") (pin "2") (pinfunction "2_2") (pintype "passive"))
      (node (ref "R13") (pin "2") (pinfunction "2_2") (pintype "passive"))
      (node (ref "R14") (pin "1") (pinfunction "1_1") (pintype "passive"))
    )
    (net (code "5") (name "ADC_3VOUT") (class "Default")
      (node (ref "3VOFB") (pin "TP") (pinfunction "P$1_TP") (pintype "bidirectional"))
      (node (ref "C54") (pin "2") (pinfunction "2_2") (pintype "passive"))
      (node (ref "IC9") (pin "42") (pinfunction "ADC2/GPIO28_42") (pintype "bidirectional"))
      (node (ref "R41") (pin "2") (pinfunction "2_2") (pintype "passive"))
      (node (ref "R42") (pin "2") (pinfunction "2_2") (pintype "passive"))
      (node (ref "R43") (pin "1") (pinfunction "1_1") (pintype "passive"))
    )
    (net (code "6") (name "ADC_VBUS") (class "Default")
      (node (ref "IC9") (pin "43") (pinfunction "ADC3/GPIO29_43") (pintype "bidirectional"))
      (node (ref "R35") (pin "2") (pinfunction "2_2") (pintype "passive"))
      (node (ref "R36") (pin "1") (pinfunction "1_1") (pintype "passive"))
    )
    (net (code "7") (name "ADC_VOUT") (class "Default")
      (node (ref "IC9") (pin "40") (pinfunction "I2C1_SDA/ADC0/GPIO26_40") (pintype "bidirectional"))
      (node (ref "R31") (pin "2") (pinfunction "2_2") (pintype "passive"))
      (node (ref "R32") (pin "1") (pinfunction "1_1") (pintype "passive"))
    )
    (net (code "8") (name "CC1") (class "Default")
      (node (ref "IC1") (pin "15") (pinfunction "CC1_15") (pintype "bidirectional"))
      (node (ref "USB1") (pin "A5") (pinfunction "CC1_A5") (pintype "bidirectional"))
    )
    (net (code "9") (name "CC2") (class "Default")
      (node (ref "IC1") (pin "14") (pinfunction "CC2_14") (pintype "bidirectional"))
      (node (ref "USB1") (pin "B5") (pinfunction "CC2_B5") (pintype "bidirectional"))
    )
    (net (code "10") (name "DSP_RES") (class "Default")
      (node (ref "DISP") (pin "14") (pinfunction "/RES_14") (pintype "input"))
    )
    (net (code "11") (name "FAULT") (class "Default")
      (node (ref "IC1") (pin "9") (pinfunction "FAULT_9") (pintype "output"))
      (node (ref "IC2") (pin "3") (pinfunction "+IN_3") (pintype "input"))
      (node (ref "IC9") (pin "19") (pinfunction "UART0_RTS/I2C1_SCL/SPI1_MOSIGPIO15_19") (pintype "bidirectional"))
    )
    (net (code "12") (name "FET_3V_EN") (class "Default")
      (node (ref "FET_3G1") (pin "TP") (pinfunction "P$1_TP") (pintype "bidirectional"))
      (node (ref "IC9") (pin "16") (pinfunction "UART0_TX/I2C0_SDA/SPI1_MISO/GPIO12_16") (pintype "bidirectional"))
      (node (ref "R46") (pin "1") (pinfunction "1_1") (pintype "passive"))
      (node (ref "R47") (pin "1") (pinfunction "1_1") (pintype "passive"))
    )
    (net (code "13") (name "FET_G") (class "Default")
      (node (ref "C4") (pin "2") (pinfunction "2_2") (pintype "passive"))
      (node (ref "D1") (pin "2") (pinfunction "A_2") (pintype "passive"))
      (node (ref "FET_G") (pin "TP") (pinfunction "P$1_TP") (pintype "bidirectional"))
      (node (ref "MOSFET1") (pin "4") (pinfunction "G_4") (pintype "passive"))
      (node (ref "MOSFET2") (pin "4") (pinfunction "G_4") (pintype "passive"))
      (node (ref "R2") (pin "2") (pinfunction "2_2") (pintype "passive"))
      (node (ref "R3") (pin "2") (pinfunction "2_2") (pintype "passive"))
      (node (ref "R4") (pin "1") (pinfunction "1_1") (pintype "passive"))
    )
    (net (code "14") (name "FET_PD_EN") (class "Default")
      (node (ref "FET_3G4") (pin "TP") (pinfunction "P$1_TP") (pintype "bidirectional"))
      (node (ref "IC9") (pin "15") (pinfunction "UART1_RTS/I2C1_SCL/SPI1_MOSI/GPIO11_15") (pintype "bidirectional"))
      (node (ref "R49") (pin "1") (pinfunction "1_1") (pintype "passive"))
      (node (ref "R51") (pin "1") (pinfunction "1_1") (pintype "passive"))
    )
    (net (code "15") (name "FLIP") (class "Default")
      (node (ref "IC1") (pin "10") (pinfunction "FLIP_10") (pintype "output"))
      (node (ref "IC3") (pin "3") (pinfunction "+IN_3") (pintype "input"))
      (node (ref "IC9") (pin "18") (pinfunction "UART0_CTS/I2C1_SDA/SPI1_SCK/GPIO14_18") (pintype "bidirectional"))
      (node (ref "R5") (pin "2") (pinfunction "2_2") (pintype "passive"))
    )
    (net (code "16") (name "GND") (class "Default")
      (node (ref "C1") (pin "2") (pinfunction "2_2") (pintype "passive"))
      (node (ref "C10") (pin "2") (pinfunction "2_2") (pintype "passive"))
      (node (ref "C11") (pin "2") (pinfunction "2_2") (pintype "passive"))
      (node (ref "C12") (pin "2") (pinfunction "2_2") (pintype "passive"))
      (node (ref "C13") (pin "2") (pinfunction "2_2") (pintype "passive"))
      (node (ref "C14") (pin "2") (pinfunction "2_2") (pintype "passive"))
      (node (ref "C15") (pin "2") (pinfunction "2_2") (pintype "passive"))
      (node (ref "C16") (pin "2") (pinfunction "2_2") (pintype "passive"))
      (node (ref "C17") (pin "2") (pinfunction "2_2") (pintype "passive"))
      (node (ref "C18") (pin "2") (pinfunction "2_2") (pintype "passive"))
      (node (ref "C19") (pin "2") (pinfunction "2_2") (pintype "passive"))
      (node (ref "C2") (pin "2") (pinfunction "2_2") (pintype "passive"))
      (node (ref "C20") (pin "2") (pinfunction "2_2") (pintype "passive"))
      (node (ref "C21") (pin "2") (pinfunction "2_2") (pintype "passive"))
      (node (ref "C22") (pin "2") (pinfunction "2_2") (pintype "passive"))
      (node (ref "C23") (pin "2") (pinfunction "2_2") (pintype "passive"))
      (node (ref "C25") (pin "2") (pinfunction "2_2") (pintype "passive"))
      (node (ref "C26") (pin "2") (pinfunction "2_2") (pintype "passive"))
      (node (ref "C28") (pin "2") (pinfunction "2_2") (pintype "passive"))
      (node (ref "C29") (pin "2") (pinfunction "2_2") (pintype "passive"))
      (node (ref "C3") (pin "2") (pinfunction "2_2") (pintype "passive"))
      (node (ref "C30") (pin "2") (pinfunction "2_2") (pintype "passive"))
      (node (ref "C31") (pin "2") (pinfunction "2_2") (pintype "passive"))
      (node (ref "C32") (pin "2") (pinfunction "2_2") (pintype "passive"))
      (node (ref "C33") (pin "2") (pinfunction "2_2") (pintype "passive"))
      (node (ref "C34") (pin "2") (pinfunction "2_2") (pintype "passive"))
      (node (ref "C35") (pin "2") (pinfunction "2_2") (pintype "passive"))
      (node (ref "C36") (pin "2") (pinfunction "2_2") (pintype "passive"))
      (node (ref "C37") (pin "2") (pinfunction "2_2") (pintype "passive"))
      (node (ref "C38") (pin "2") (pinfunction "2_2") (pintype "passive"))
      (node (ref "C39") (pin "2") (pinfunction "2_2") (pintype "passive"))
      (node (ref "C40") (pin "2") (pinfunction "2_2") (pintype "passive"))
      (node (ref "C41") (pin "2") (pinfunction "2_2") (pintype "passive"))
      (node (ref "C42") (pin "2") (pinfunction "2_2") (pintype "passive"))
      (node (ref "C43") (pin "2") (pinfunction "2_2") (pintype "passive"))
      (node (ref "C44") (pin "2") (pinfunction "2_2") (pintype "passive"))
      (node (ref "C5") (pin "2") (pinfunction "2_2") (pintype "passive"))
      (node (ref "C51") (pin "2") (pinfunction "2_2") (pintype "passive"))
      (node (ref "C52") (pin "2") (pinfunction "2_2") (pintype "passive"))
      (node (ref "C55") (pin "2") (pinfunction "2_2") (pintype "passive"))
      (node (ref "C56") (pin "2") (pinfunction "2_2") (pintype "passive"))
      (node (ref "C57") (pin "2") (pinfunction "2_2") (pintype "passive"))
      (node (ref "C6") (pin "2") (pinfunction "2_2") (pintype "passive"))
      (node (ref "C63") (pin "2") (pinfunction "2_2") (pintype "passive"))
      (node (ref "C64") (pin "2") (pinfunction "2_2") (pintype "passive"))
      (node (ref "C65") (pin "2") (pinfunction "2_2") (pintype "passive"))
      (node (ref "C67") (pin "2") (pinfunction "2_2") (pintype "passive"))
      (node (ref "C7") (pin "2") (pinfunction "2_2") (pintype "passive"))
      (node (ref "C8") (pin "2") (pinfunction "2_2") (pintype "passive"))
      (node (ref "C9") (pin "2") (pinfunction "2_2") (pintype "passive"))
      (node (ref "CON1") (pin "P$2") (pinfunction "2_P$2") (pintype "bidirectional"))
      (node (ref "CON1") (pin "P$4") (pinfunction "4_P$4") (pintype "bidirectional"))
      (node (ref "CON2") (pin "P$2") (pinfunction "2_P$2") (pintype "bidirectional"))
      (node (ref "CON2") (pin "P$4") (pinfunction "4_P$4") (pintype "bidirectional"))
      (node (ref "CON3") (pin "P$2") (pinfunction "2_P$2") (pintype "bidirectional"))
      (node (ref "CON3") (pin "P$4") (pinfunction "4_P$4") (pintype "bidirectional"))
      (node (ref "CON4") (pin "P$2") (pinfunction "2_P$2") (pintype "bidirectional"))
      (node (ref "CON4") (pin "P$4") (pinfunction "4_P$4") (pintype "bidirectional"))
      (node (ref "D6") (pin "2") (pinfunction "A_2") (pintype "passive"))
      (node (ref "DISP") (pin "1") (pinfunction "NC(GND)_1") (pintype "input"))
      (node (ref "DISP") (pin "10") (pinfunction "BS0_10") (pintype "input"))
      (node (ref "DISP") (pin "12") (pinfunction "BS2_12") (pintype "input"))
      (node (ref "DISP") (pin "15") (pinfunction "DC/I2C_SA0_15") (pintype "input"))
      (node (ref "DISP") (pin "30") (pinfunction "NC(GND)_30") (pintype "input"))
      (node (ref "DISP") (pin "8") (pinfunction "VSS_8") (pintype "power_in"))
      (node (ref "ESD1") (pin "1") (pinfunction "A_1") (pintype "bidirectional"))
      (node (ref "GND-3") (pin "TP") (pinfunction "P$1_TP") (pintype "bidirectional"))
      (node (ref "I-SET") (pin "2") (pinfunction "2_2") (pintype "passive"))
      (node (ref "I-SET") (pin "C") (pinfunction "COM_C") (pintype "passive"))
      (node (ref "IC1") (pin "19") (pinfunction "GND_19") (pintype "power_in"))
      (node (ref "IC1") (pin "22") (pinfunction "VSS_22") (pintype "power_in"))
      (node (ref "IC1") (pin "25") (pinfunction "PAD_25") (pintype "power_in"))
      (node (ref "IC10") (pin "4") (pinfunction "GND_4") (pintype "bidirectional"))
      (node (ref "IC11") (pin "4") (pinfunction "GND_4") (pintype "power_in"))
      (node (ref "IC12") (pin "1") (pinfunction "A0_1") (pintype "bidirectional"))
      (node (ref "IC12") (pin "2") (pinfunction "A1_2") (pintype "bidirectional"))
      (node (ref "IC12") (pin "3") (pinfunction "A2_3") (pintype "bidirectional"))
      (node (ref "IC12") (pin "4") (pinfunction "GND_4") (pintype "power_in"))
      (node (ref "IC12") (pin "7") (pinfunction "WP_7") (pintype "bidirectional"))
      (node (ref "IC12") (pin "9") (pinfunction "GND_9") (pintype "power_in"))
      (node (ref "IC13") (pin "3") (pinfunction "GND_3") (pintype "bidirectional"))
      (node (ref "IC13") (pin "7") (pinfunction "A0_7") (pintype "bidirectional"))
      (node (ref "IC13") (pin "8") (pinfunction "A1_8") (pintype "bidirectional"))
      (node (ref "IC17") (pin "4") (pinfunction "GND_4") (pintype "bidirectional"))
      (node (ref "IC2") (pin "5") (pinfunction "V-_5") (pintype "power_in"))
      (node (ref "IC3") (pin "5") (pinfunction "V-_5") (pintype "power_in"))
      (node (ref "IC4") (pin "10") (pinfunction "GND_10") (pintype "power_in"))
      (node (ref "IC5") (pin "5") (pinfunction "V-_5") (pintype "power_in"))
      (node (ref "IC6") (pin "5") (pinfunction "V-_5") (pintype "power_in"))
      (node (ref "IC7") (pin "5") (pinfunction "V-_5") (pintype "power_in"))
      (node (ref "IC8") (pin "5") (pinfunction "V-_5") (pintype "power_in"))
      (node (ref "IC9") (pin "47") (pinfunction "VREG_PGND_47") (pintype "power_in"))
      (node (ref "IC9") (pin "61") (pinfunction "GND_61") (pintype "power_in"))
      (node (ref "R1") (pin "2") (pinfunction "2_2") (pintype "passive"))
      (node (ref "R10") (pin "2") (pinfunction "2_2") (pintype "passive"))
      (node (ref "R14") (pin "2") (pinfunction "2_2") (pintype "passive"))
      (node (ref "R28") (pin "2") (pinfunction "2_2") (pintype "passive"))
      (node (ref "R32") (pin "2") (pinfunction "2_2") (pintype "passive"))
      (node (ref "R36") (pin "2") (pinfunction "2_2") (pintype "passive"))
      (node (ref "R39") (pin "2") (pinfunction "2_2") (pintype "passive"))
      (node (ref "R43") (pin "2") (pinfunction "2_2") (pintype "passive"))
      (node (ref "R47") (pin "2") (pinfunction "2_2") (pintype "passive"))
      (node (ref "R51") (pin "2") (pinfunction "2_2") (pintype "passive"))
      (node (ref "T2") (pin "2") (pinfunction "S_2") (pintype "passive"))
      (node (ref "T4") (pin "2") (pinfunction "S_2") (pintype "passive"))
      (node (ref "USB1") (pin "GND") (pinfunction "GND_GND") (pintype "power_in"))
      (node (ref "USB1") (pin "GND2") (pinfunction "GND_GND2") (pintype "power_in"))
      (node (ref "V-SET") (pin "2") (pinfunction "2_2") (pintype "passive"))
      (node (ref "V-SET") (pin "C") (pinfunction "COM_C") (pintype "passive"))
      (node (ref "X1") (pin "2") (pinfunction "GND_2") (pintype "passive"))
      (node (ref "X1") (pin "4") (pinfunction "GND_4") (pintype "passive"))
    )
    (net (code "17") (name "GPIO") (class "Default")
      (node (ref "IC1") (pin "8") (pinfunction "GPIO_1_8") (pintype "bidirectional"))
    )
    (net (code "18") (name "I2C0_SCL") (class "Default")
      (node (ref "IC1") (pin "13") (pinfunction "HPI_SCL_13") (pintype "bidirectional"))
      (node (ref "IC13") (pin "5") (pinfunction "SCL_5") (pintype "bidirectional"))
      (node (ref "IC4") (pin "2") (pinfunction "SCL_2") (pintype "bidirectional"))
      (node (ref "IC9") (pin "8") (pinfunction "UART1_RX/#I2C0_SCL/SPI0_CS/GPIO5_8") (pintype "bidirectional"))
      (node (ref "R38") (pin "1") (pinfunction "1_1") (pintype "passive"))
    )
    (net (code "19") (name "I2C0_SDA") (class "Default")
      (node (ref "IC1") (pin "12") (pinfunction "HPI_SDA_12") (pintype "bidirectional"))
      (node (ref "IC13") (pin "6") (pinfunction "SDA_6") (pintype "bidirectional"))
      (node (ref "IC4") (pin "3") (pinfunction "SDA_3") (pintype "bidirectional"))
      (node (ref "IC9") (pin "7") (pinfunction "UART1_TX/#I2C0_SDA/SPI0_MISO/GPIO4_7") (pintype "bidirectional"))
      (node (ref "R38") (pin "2") (pinfunction "2_2") (pintype "passive"))
    )
    (net (code "20") (name "I2C1_SCL") (class "Default")
      (node (ref "DISP") (pin "18") (pinfunction "D0/SPI_SCLK/I2C_SCK_18") (pintype "bidirectional"))
      (node (ref "IC12") (pin "6") (pinfunction "SCL_6") (pintype "bidirectional"))
      (node (ref "IC9") (pin "5") (pinfunction "UART0_RTS/I2C1_SCL/SPI0_MOSI/GPIO3_5") (pintype "bidirectional"))
      (node (ref "R38") (pin "3") (pinfunction "3_3") (pintype "passive"))
    )
    (net (code "21") (name "I2C1_SDA") (class "Default")
      (node (ref "DISP") (pin "19") (pinfunction "D1/SPI_SDIN/I2C_SDA_19") (pintype "bidirectional"))
      (node (ref "DISP") (pin "20") (pinfunction "D2/I2C_SDA_20") (pintype "bidirectional"))
      (node (ref "IC12") (pin "5") (pinfunction "SDA_5") (pintype "bidirectional"))
      (node (ref "IC9") (pin "4") (pinfunction "UART0_CTS/I2C1_SDA/SPI0_SCK/GPIO2_4") (pintype "bidirectional"))
      (node (ref "R38") (pin "4") (pinfunction "4_4") (pintype "passive"))
    )
    (net (code "22") (name "INT") (class "Default")
      (node (ref "IC1") (pin "7") (pinfunction "HPI_INT_7") (pintype "output"))
      (node (ref "IC9") (pin "17") (pinfunction "UART0_RX/I2C0_SCL/SPI1_CS/GPIO13_17") (pintype "bidirectional"))
    )
    (net (code "23") (name "ISINK_C") (class "Default")
      (node (ref "IC") (pin "TP") (pinfunction "P$1_TP") (pintype "bidirectional"))
      (node (ref "IC1") (pin "5") (pinfunction "ISNK_COARSE_5") (pintype "input"))
      (node (ref "IC7") (pin "1") (pinfunction "OUT_1") (pintype "output"))
      (node (ref "IC7") (pin "4") (pinfunction "-IN_4") (pintype "input"))
    )
    (net (code "24") (name "ISINK_F") (class "Default")
      (node (ref "IC1") (pin "6") (pinfunction "ISNK_FINE_6") (pintype "input"))
      (node (ref "IC8") (pin "1") (pinfunction "OUT_1") (pintype "output"))
      (node (ref "IC8") (pin "4") (pinfunction "-IN_4") (pintype "input"))
      (node (ref "IF") (pin "TP") (pinfunction "P$1_TP") (pintype "bidirectional"))
    )
    (net (code "25") (name "Net-(C3-Pad1)") (class "Default")
      (node (ref "C3") (pin "1") (pinfunction "1_1") (pintype "passive"))
      (node (ref "R1") (pin "1") (pinfunction "1_1") (pintype "passive"))
      (node (ref "USB1") (pin "SHLD1") (pinfunction "SHILED_SHLD1") (pintype "power_in"))
      (node (ref "USB1") (pin "SHLD2") (pinfunction "SHILED_SHLD2") (pintype "power_in"))
      (node (ref "USB1") (pin "SHLD3") (pinfunction "SHILED_SHLD3") (pintype "power_in"))
      (node (ref "USB1") (pin "SHLD4") (pinfunction "SHILED_SHLD4") (pintype "power_in"))
    )
    (net (code "26") (name "Net-(C24-Pad1)") (class "Default")
      (node (ref "C24") (pin "1") (pinfunction "1_1") (pintype "passive"))
      (node (ref "R11") (pin "1") (pinfunction "1_1") (pintype "passive"))
    )
    (net (code "27") (name "Net-(C53-Pad1)") (class "Default")
      (node (ref "C53") (pin "1") (pinfunction "1_1") (pintype "passive"))
      (node (ref "R40") (pin "1") (pinfunction "1_1") (pintype "passive"))
    )
    (net (code "28") (name "Net-(D1-C)") (class "Default")
      (node (ref "D1") (pin "1") (pinfunction "C_1") (pintype "passive"))
      (node (ref "MOSFET1") (pin "1") (pinfunction "S_2_1") (pintype "passive"))
      (node (ref "MOSFET1") (pin "2") (pinfunction "S_3_2") (pintype "passive"))
      (node (ref "MOSFET1") (pin "3") (pinfunction "S_3") (pintype "passive"))
      (node (ref "MOSFET2") (pin "1") (pinfunction "S_2_1") (pintype "passive"))
      (node (ref "MOSFET2") (pin "2") (pinfunction "S_3_2") (pintype "passive"))
      (node (ref "MOSFET2") (pin "3") (pinfunction "S_3") (pintype "passive"))
      (node (ref "R3") (pin "1") (pinfunction "1_1") (pintype "passive"))
    )
    (net (code "29") (name "Net-(D6-C)") (class "Default")
      (node (ref "C58") (pin "2") (pinfunction "2_2") (pintype "passive"))
      (node (ref "D6") (pin "1") (pinfunction "C_1") (pintype "passive"))
      (node (ref "FET_3G3") (pin "TP") (pinfunction "P$1_TP") (pintype "bidirectional"))
      (node (ref "MOSFET4") (pin "4") (pinfunction "G_4") (pintype "passive"))
      (node (ref "R48") (pin "2") (pinfunction "2_2") (pintype "passive"))
      (node (ref "T4") (pin "3") (pinfunction "D_3") (pintype "passive"))
    )
    (net (code "30") (name "Net-(DAC1-P$1)") (class "Default")
      (node (ref "DAC1") (pin "TP") (pinfunction "P$1_TP") (pintype "bidirectional"))
      (node (ref "IC4") (pin "6") (pinfunction "VOUT_A_6") (pintype "output"))
      (node (ref "IC5") (pin "3") (pinfunction "+IN_3") (pintype "input"))
    )
    (net (code "31") (name "Net-(DAC2-P$1)") (class "Default")
      (node (ref "DAC2") (pin "TP") (pinfunction "P$1_TP") (pintype "bidirectional"))
      (node (ref "IC4") (pin "7") (pinfunction "VOUT_B_7") (pintype "output"))
      (node (ref "IC6") (pin "3") (pinfunction "+IN_3") (pintype "input"))
    )
    (net (code "32") (name "Net-(DAC3-P$1)") (class "Default")
      (node (ref "DAC3") (pin "TP") (pinfunction "P$1_TP") (pintype "bidirectional"))
      (node (ref "IC4") (pin "8") (pinfunction "VOUT_C_8") (pintype "output"))
      (node (ref "IC7") (pin "3") (pinfunction "+IN_3") (pintype "input"))
    )
    (net (code "33") (name "Net-(DAC4-P$1)") (class "Default")
      (node (ref "DAC4") (pin "TP") (pinfunction "P$1_TP") (pintype "bidirectional"))
      (node (ref "IC4") (pin "9") (pinfunction "VOUT_D_9") (pintype "output"))
      (node (ref "IC8") (pin "3") (pinfunction "+IN_3") (pintype "input"))
    )
    (net (code "34") (name "Net-(DISP-C1N)") (class "Default")
      (node (ref "C62") (pin "2") (pinfunction "2_2") (pintype "passive"))
      (node (ref "DISP") (pin "5") (pinfunction "C1N_5") (pintype "input"))
    )
    (net (code "35") (name "Net-(DISP-C1P)") (class "Default")
      (node (ref "C62") (pin "1") (pinfunction "1_1") (pintype "passive"))
      (node (ref "DISP") (pin "4") (pinfunction "C1P_4") (pintype "input"))
    )
    (net (code "36") (name "Net-(DISP-C2N)") (class "Default")
      (node (ref "C61") (pin "1") (pinfunction "1_1") (pintype "passive"))
      (node (ref "DISP") (pin "3") (pinfunction "C2N_3") (pintype "input"))
    )
    (net (code "37") (name "Net-(DISP-C2P)") (class "Default")
      (node (ref "C61") (pin "2") (pinfunction "2_2") (pintype "passive"))
      (node (ref "DISP") (pin "2") (pinfunction "C2P_2") (pintype "input"))
    )
    (net (code "38") (name "Net-(DISP-VCC)") (class "Default")
      (node (ref "C65") (pin "1") (pinfunction "1_1") (pintype "passive"))
      (node (ref "DISP") (pin "28") (pinfunction "VCC_28") (pintype "power_in"))
    )
    (net (code "39") (name "Net-(DISP-VCOMH)") (class "Default")
      (node (ref "DISP") (pin "27") (pinfunction "VCOMH_27") (pintype "output"))
      (node (ref "R28") (pin "1") (pinfunction "1_1") (pintype "passive"))
    )
    (net (code "40") (name "Net-(DISP-VLSS)") (class "Default")
      (node (ref "C64") (pin "1") (pinfunction "1_1") (pintype "passive"))
      (node (ref "DISP") (pin "29") (pinfunction "VLSS_29") (pintype "power_in"))
    )
    (net (code "41") (name "Net-(DISP-{slash}CS)") (class "Default")
      (node (ref "DISP") (pin "13") (pinfunction "/CS_13") (pintype "input"))
      (node (ref "R27") (pin "2") (pinfunction "2_2") (pintype "passive"))
    )
    (net (code "42") (name "Net-(FAULT-PadA)") (class "Default")
      (node (ref "FAULT") (pin "A") (pinfunction "A_A") (pintype "passive"))
      (node (ref "R6") (pin "2") (pinfunction "2_2") (pintype "passive"))
    )
    (net (code "43") (name "Net-(FET_3G2-P$1)") (class "Default")
      (node (ref "C60") (pin "2") (pinfunction "2_2") (pintype "passive"))
      (node (ref "FET_3G2") (pin "TP") (pinfunction "P$1_TP") (pintype "bidirectional"))
      (node (ref "MOSFET3") (pin "4") (pinfunction "G_4") (pintype "passive"))
      (node (ref "R45") (pin "2") (pinfunction "2_2") (pintype "passive"))
      (node (ref "T2") (pin "3") (pinfunction "D_3") (pintype "passive"))
    )
    (net (code "44") (name "Net-(FLIP-PadA)") (class "Default")
      (node (ref "FLIP") (pin "A") (pinfunction "A_A") (pintype "passive"))
      (node (ref "R7") (pin "2") (pinfunction "2_2") (pintype "passive"))
    )
    (net (code "45") (name "Net-(IC1-VBUS_FET_EN)") (class "Default")
      (node (ref "IC1") (pin "3") (pinfunction "VBUS_FET_EN_3") (pintype "output"))
      (node (ref "R4") (pin "2") (pinfunction "2_2") (pintype "passive"))
    )
    (net (code "46") (name "Net-(IC1-VCCD)") (class "Default")
      (node (ref "C8") (pin "1") (pinfunction "1_1") (pintype "passive"))
      (node (ref "IC1") (pin "24") (pinfunction "VCCD_24") (pintype "power_in"))
    )
    (net (code "47") (name "Net-(IC2--IN)") (class "Default")
      (node (ref "FAULT") (pin "C") (pinfunction "C_C") (pintype "passive"))
      (node (ref "IC2") (pin "1") (pinfunction "OUT_1") (pintype "output"))
      (node (ref "IC2") (pin "4") (pinfunction "-IN_4") (pintype "input"))
    )
    (net (code "48") (name "Net-(IC3--IN)") (class "Default")
      (node (ref "FLIP") (pin "C") (pinfunction "C_C") (pintype "passive"))
      (node (ref "IC3") (pin "1") (pinfunction "OUT_1") (pintype "output"))
      (node (ref "IC3") (pin "4") (pinfunction "-IN_4") (pintype "input"))
    )
    (net (code "49") (name "Net-(IC9-RUN)") (class "Default")
      (node (ref "IC9") (pin "26") (pinfunction "RUN_26") (pintype "bidirectional"))
      (node (ref "R50") (pin "2") (pinfunction "2_2") (pintype "passive"))
      (node (ref "RUN") (pin "TP") (pinfunction "P$1_TP") (pintype "bidirectional"))
    )
    (net (code "50") (name "Net-(IC9-USB_DM)") (class "Default")
      (node (ref "IC9") (pin "51") (pinfunction "USB_DM_51") (pintype "bidirectional"))
      (node (ref "R21") (pin "2") (pinfunction "2_2") (pintype "passive"))
    )
    (net (code "51") (name "Net-(IC9-USB_DP)") (class "Default")
      (node (ref "IC9") (pin "52") (pinfunction "USB_DP_52") (pintype "bidirectional"))
      (node (ref "R22") (pin "2") (pinfunction "2_2") (pintype "passive"))
    )
    (net (code "52") (name "Net-(IC9-VREG_AVDD)") (class "Default")
      (node (ref "IC9") (pin "46") (pinfunction "VREG_AVDD_46") (pintype "power_in"))
      (node (ref "R8") (pin "1") (pinfunction "1_1") (pintype "passive"))
    )
    (net (code "53") (name "Net-(IC9-VREG_LX)") (class "Default")
      (node (ref "IC9") (pin "48") (pinfunction "VREG_LX_48") (pintype "power_in"))
      (node (ref "L1") (pin "1") (pinfunction "1_1") (pintype "passive"))
    )
    (net (code "54") (name "Net-(IC10-AAM)") (class "Default")
      (node (ref "IC10") (pin "1") (pinfunction "AAM_1") (pintype "bidirectional"))
      (node (ref "R10") (pin "1") (pinfunction "1_1") (pintype "passive"))
      (node (ref "R15") (pin "2") (pinfunction "2_2") (pintype "passive"))
    )
    (net (code "55") (name "Net-(IC10-BST)") (class "Default")
      (node (ref "IC10") (pin "5") (pinfunction "BST_5") (pintype "bidirectional"))
      (node (ref "R11") (pin "2") (pinfunction "2_2") (pintype "passive"))
    )
    (net (code "56") (name "Net-(IC10-EN)") (class "Default")
      (node (ref "IC10") (pin "6") (pinfunction "EN_6") (pintype "bidirectional"))
      (node (ref "R9") (pin "2") (pinfunction "2_2") (pintype "passive"))
    )
    (net (code "57") (name "Net-(IC10-FB)") (class "Default")
      (node (ref "IC10") (pin "8") (pinfunction "FB_8") (pintype "bidirectional"))
      (node (ref "R12") (pin "1") (pinfunction "1_1") (pintype "passive"))
    )
    (net (code "58") (name "Net-(IC10-SW)") (class "Default")
      (node (ref "C24") (pin "2") (pinfunction "2_2") (pintype "passive"))
      (node (ref "IC10") (pin "3") (pinfunction "SW_3") (pintype "bidirectional"))
      (node (ref "L2") (pin "1") (pinfunction "1_1") (pintype "passive"))
      (node (ref "SW3") (pin "TP") (pinfunction "P$1_TP") (pintype "bidirectional"))
    )
    (net (code "59") (name "Net-(IC10-VCC)") (class "Default")
      (node (ref "C23") (pin "1") (pinfunction "1_1") (pintype "passive"))
      (node (ref "IC10") (pin "7") (pinfunction "VCC_7") (pintype "bidirectional"))
      (node (ref "R15") (pin "1") (pinfunction "1_1") (pintype "passive"))
    )
    (net (code "60") (name "Net-(IC17-AAM)") (class "Default")
      (node (ref "IC17") (pin "1") (pinfunction "AAM_1") (pintype "bidirectional"))
      (node (ref "R39") (pin "1") (pinfunction "1_1") (pintype "passive"))
      (node (ref "R44") (pin "2") (pinfunction "2_2") (pintype "passive"))
    )
    (net (code "61") (name "Net-(IC17-BST)") (class "Default")
      (node (ref "IC17") (pin "5") (pinfunction "BST_5") (pintype "bidirectional"))
      (node (ref "R40") (pin "2") (pinfunction "2_2") (pintype "passive"))
    )
    (net (code "62") (name "Net-(IC17-EN)") (class "Default")
      (node (ref "IC17") (pin "6") (pinfunction "EN_6") (pintype "bidirectional"))
      (node (ref "R37") (pin "2") (pinfunction "2_2") (pintype "passive"))
    )
    (net (code "63") (name "Net-(IC17-FB)") (class "Default")
      (node (ref "IC17") (pin "8") (pinfunction "FB_8") (pintype "bidirectional"))
      (node (ref "R41") (pin "1") (pinfunction "1_1") (pintype "passive"))
    )
    (net (code "64") (name "Net-(IC17-SW)") (class "Default")
      (node (ref "C53") (pin "2") (pinfunction "2_2") (pintype "passive"))
      (node (ref "IC17") (pin "3") (pinfunction "SW_3") (pintype "bidirectional"))
      (node (ref "L3") (pin "1") (pinfunction "1_1") (pintype "passive"))
      (node (ref "SW3O") (pin "TP") (pinfunction "P$1_TP") (pintype "bidirectional"))
    )
    (net (code "65") (name "Net-(IC17-VCC)") (class "Default")
      (node (ref "C52") (pin "1") (pinfunction "1_1") (pintype "passive"))
      (node (ref "IC17") (pin "7") (pinfunction "VCC_7") (pintype "bidirectional"))
      (node (ref "R44") (pin "1") (pinfunction "1_1") (pintype "passive"))
    )
    (net (code "66") (name "Net-(T2-G)") (class "Default")
      (node (ref "R46") (pin "2") (pinfunction "2_2") (pintype "passive"))
      (node (ref "T2") (pin "1") (pinfunction "G_1") (pintype "passive"))
    )
    (net (code "67") (name "Net-(T4-G)") (class "Default")
      (node (ref "R49") (pin "2") (pinfunction "2_2") (pintype "passive"))
      (node (ref "T4") (pin "1") (pinfunction "G_1") (pintype "passive"))
    )
    (net (code "68") (name "Net-(X1-2)") (class "Default")
      (node (ref "C20") (pin "1") (pinfunction "1_1") (pintype "passive"))
      (node (ref "R16") (pin "1") (pinfunction "1_1") (pintype "passive"))
      (node (ref "X1") (pin "3") (pinfunction "2_3") (pintype "passive"))
    )
    (net (code "69") (name "QSPI_SCLK") (class "Default")
      (node (ref "IC11") (pin "6") (pinfunction "CLK_6") (pintype "bidirectional"))
      (node (ref "IC9") (pin "56") (pinfunction "QSPI_SCLK_56") (pintype "bidirectional"))
    )
    (net (code "70") (name "QSPI_SD0") (class "Default")
      (node (ref "IC11") (pin "5") (pinfunction "DI/IO0_5") (pintype "bidirectional"))
      (node (ref "IC9") (pin "57") (pinfunction "QSPI_SD0_57") (pintype "bidirectional"))
    )
    (net (code "71") (name "QSPI_SD1") (class "Default")
      (node (ref "IC11") (pin "2") (pinfunction "DO/IO1_2") (pintype "bidirectional"))
      (node (ref "IC9") (pin "59") (pinfunction "QSPI_SD1_59") (pintype "bidirectional"))
    )
    (net (code "72") (name "QSPI_SD2") (class "Default")
      (node (ref "IC11") (pin "3") (pinfunction "~{WP}/IO2_3") (pintype "bidirectional"))
      (node (ref "IC9") (pin "58") (pinfunction "QSPI_SD2_58") (pintype "bidirectional"))
    )
    (net (code "73") (name "QSPI_SD3") (class "Default")
      (node (ref "IC11") (pin "7") (pinfunction "~{HOLD}/IO3_7") (pintype "bidirectional"))
      (node (ref "IC9") (pin "55") (pinfunction "QSPI_SD3_55") (pintype "bidirectional"))
    )
    (net (code "74") (name "RE-I1") (class "Default")
      (node (ref "I-SET") (pin "A") (pinfunction "A_A") (pintype "passive"))
      (node (ref "R24") (pin "2") (pinfunction "2_2") (pintype "passive"))
    )
    (net (code "75") (name "RE-I2") (class "Default")
      (node (ref "I-SET") (pin "B") (pinfunction "B_B") (pintype "passive"))
      (node (ref "R25") (pin "2") (pinfunction "2_2") (pintype "passive"))
    )
    (net (code "76") (name "RE-SWI") (class "Default")
      (node (ref "C43") (pin "1") (pinfunction "1_1") (pintype "passive"))
      (node (ref "I-SET") (pin "1") (pinfunction "1_1") (pintype "passive"))
      (node (ref "R26") (pin "2") (pinfunction "2_2") (pintype "passive"))
    )
    (net (code "77") (name "RE-SWV") (class "Default")
      (node (ref "C44") (pin "1") (pinfunction "1_1") (pintype "passive"))
      (node (ref "R23") (pin "2") (pinfunction "2_2") (pintype "passive"))
      (node (ref "V-SET") (pin "1") (pinfunction "1_1") (pintype "passive"))
    )
    (net (code "78") (name "RE-V1") (class "Default")
      (node (ref "R19") (pin "2") (pinfunction "2_2") (pintype "passive"))
      (node (ref "V-SET") (pin "A") (pinfunction "A_A") (pintype "passive"))
    )
    (net (code "79") (name "RE-V2") (class "Default")
      (node (ref "R20") (pin "2") (pinfunction "2_2") (pintype "passive"))
      (node (ref "V-SET") (pin "B") (pinfunction "B_B") (pintype "passive"))
    )
    (net (code "80") (name "RP_XI") (class "Default")
      (node (ref "C19") (pin "1") (pinfunction "1_1") (pintype "passive"))
      (node (ref "IC9") (pin "21") (pinfunction "XIN_21") (pintype "input"))
      (node (ref "X1") (pin "1") (pinfunction "1_1") (pintype "passive"))
    )
    (net (code "81") (name "RP_XO") (class "Default")
      (node (ref "IC9") (pin "22") (pinfunction "XOUT_22") (pintype "output"))
      (node (ref "R16") (pin "2") (pinfunction "2_2") (pintype "passive"))
    )
    (net (code "82") (name "SAFE_PWR_EN") (class "Default")
      (node (ref "IC1") (pin "4") (pinfunction "SAFE_PWR_EN_4") (pintype "output"))
    )
    (net (code "83") (name "SPI0_CS") (class "Default")
      (node (ref "IC9") (pin "28") (pinfunction "UART0_RX/I2C0_SCL/#SPI0_CS/GPIO17_28") (pintype "bidirectional"))
    )
    (net (code "84") (name "SPI0_MISO") (class "Default")
      (node (ref "IC9") (pin "27") (pinfunction "UART0_TX/I2C0_SDA/#SPI0_MISO/GPIO16_27") (pintype "bidirectional"))
    )
    (net (code "85") (name "SPI0_MOSI") (class "Default")
      (node (ref "IC9") (pin "31") (pinfunction "UART0_RTS/I2C1_SCL/#SPI0_MOSI/GPIO19_31") (pintype "bidirectional"))
    )
    (net (code "86") (name "SPI0_SCK") (class "Default")
      (node (ref "IC9") (pin "29") (pinfunction "UART0_CTS/I2C1_SDA/#SPI0_SCK/GPIO18_29") (pintype "bidirectional"))
    )
    (net (code "87") (name "SWCLK") (class "Default")
      (node (ref "IC9") (pin "24") (pinfunction "SWCLK_24") (pintype "bidirectional"))
      (node (ref "SWCLK") (pin "TP") (pinfunction "P$1_TP") (pintype "bidirectional"))
    )
    (net (code "88") (name "SWDIO") (class "Default")
      (node (ref "IC9") (pin "25") (pinfunction "SWDIO_25") (pintype "bidirectional"))
      (node (ref "SWDIO") (pin "TP") (pinfunction "P$1_TP") (pintype "bidirectional"))
    )
    (net (code "89") (name "UART0_RX") (class "Default")
      (node (ref "IC9") (pin "2") (pinfunction "#UART0_TX/I2C0_SDA/SPI0_MISO/GPIO0_2") (pintype "bidirectional"))
      (node (ref "RX") (pin "TP") (pinfunction "P$1_TP") (pintype "bidirectional"))
    )
    (net (code "90") (name "UART0_TX") (class "Default")
      (node (ref "IC9") (pin "3") (pinfunction "#UART0_RX/I2C0_SCL/SPI0_CS/GPIO1_3") (pintype "bidirectional"))
      (node (ref "TX") (pin "TP") (pinfunction "P$1_TP") (pintype "bidirectional"))
    )
    (net (code "91") (name "USB_DP_N") (class "Default")
      (node (ref "ESD1") (pin "3") (pinfunction "C2_3") (pintype "bidirectional"))
      (node (ref "R21") (pin "1") (pinfunction "1_1") (pintype "passive"))
      (node (ref "USB1") (pin "A7") (pinfunction "D-_A7") (pintype "bidirectional"))
      (node (ref "USB1") (pin "B7") (pinfunction "D-_B7") (pintype "bidirectional"))
    )
    (net (code "92") (name "USB_DP_P") (class "Default")
      (node (ref "ESD1") (pin "2") (pinfunction "C1_2") (pintype "bidirectional"))
      (node (ref "R22") (pin "1") (pinfunction "1_1") (pintype "passive"))
      (node (ref "USB1") (pin "A6") (pinfunction "D+_A6") (pintype "bidirectional"))
      (node (ref "USB1") (pin "B6") (pinfunction "D+_B6") (pintype "bidirectional"))
    )
    (net (code "93") (name "VBUS") (class "Default")
      (node (ref "C1") (pin "1") (pinfunction "1_1") (pintype "passive"))
      (node (ref "C2") (pin "1") (pinfunction "1_1") (pintype "passive"))
      (node (ref "C22") (pin "1") (pinfunction "1_1") (pintype "passive"))
      (node (ref "C35") (pin "1") (pinfunction "1_1") (pintype "passive"))
      (node (ref "C4") (pin "1") (pinfunction "1_1") (pintype "passive"))
      (node (ref "C51") (pin "1") (pinfunction "1_1") (pintype "passive"))
      (node (ref "C55") (pin "1") (pinfunction "1_1") (pintype "passive"))
      (node (ref "ESD1") (pin "4") (pinfunction "C3_4") (pintype "bidirectional"))
      (node (ref "IC1") (pin "18") (pinfunction "VBUS_IN_18") (pintype "input"))
      (node (ref "IC10") (pin "2") (pinfunction "IN_2") (pintype "bidirectional"))
      (node (ref "IC17") (pin "2") (pinfunction "IN_2") (pintype "bidirectional"))
      (node (ref "MOSFET1") (pin "5") (pinfunction "D_2_5") (pintype "passive"))
      (node (ref "MOSFET1") (pin "6") (pinfunction "D_3_6") (pintype "passive"))
      (node (ref "MOSFET1") (pin "7") (pinfunction "D_4_7") (pintype "passive"))
      (node (ref "MOSFET1") (pin "8") (pinfunction "D_8") (pintype "passive"))
      (node (ref "MOSFET1") (pin "9") (pinfunction "D_9") (pintype "passive"))
      (node (ref "R2") (pin "1") (pinfunction "1_1") (pintype "passive"))
      (node (ref "R35") (pin "1") (pinfunction "1_1") (pintype "passive"))
      (node (ref "R37") (pin "1") (pinfunction "1_1") (pintype "passive"))
      (node (ref "R9") (pin "1") (pinfunction "1_1") (pintype "passive"))
      (node (ref "USB1") (pin "VBUS1") (pinfunction "VBUS_VBUS1") (pintype "power_in"))
      (node (ref "USB1") (pin "VBUS2") (pinfunction "VBUS_VBUS2") (pintype "power_in"))
      (node (ref "VBUS") (pin "TP") (pinfunction "P$1_TP") (pintype "bidirectional"))
    )
    (net (code "94") (name "VBUS_MAX") (class "Default")
      (node (ref "IC1") (pin "2") (pinfunction "VBUS_MAX_2") (pintype "input"))
      (node (ref "IC6") (pin "1") (pinfunction "OUT_1") (pintype "output"))
      (node (ref "IC6") (pin "4") (pinfunction "-IN_4") (pintype "input"))
      (node (ref "VMAX") (pin "TP") (pinfunction "P$1_TP") (pintype "bidirectional"))
    )
    (net (code "95") (name "VBUS_MIN") (class "Default")
      (node (ref "IC1") (pin "1") (pinfunction "VBUS_MIN_1") (pintype "input"))
      (node (ref "IC5") (pin "1") (pinfunction "OUT_1") (pintype "output"))
      (node (ref "IC5") (pin "4") (pinfunction "-IN_4") (pintype "input"))
      (node (ref "VMIN") (pin "TP") (pinfunction "P$1_TP") (pintype "bidirectional"))
    )
    (net (code "96") (name "VOUT-1") (class "Default")
      (node (ref "C63") (pin "1") (pinfunction "1_1") (pintype "passive"))
      (node (ref "IC13") (pin "1") (pinfunction "IN+_1") (pintype "bidirectional"))
      (node (ref "MOSFET3") (pin "5") (pinfunction "D_2_5") (pintype "passive"))
      (node (ref "MOSFET3") (pin "6") (pinfunction "D_3_6") (pintype "passive"))
      (node (ref "MOSFET3") (pin "7") (pinfunction "D_4_7") (pintype "passive"))
      (node (ref "MOSFET3") (pin "8") (pinfunction "D_8") (pintype "passive"))
      (node (ref "MOSFET3") (pin "9") (pinfunction "D_9") (pintype "passive"))
      (node (ref "MOSFET4") (pin "5") (pinfunction "D_2_5") (pintype "passive"))
      (node (ref "MOSFET4") (pin "6") (pinfunction "D_3_6") (pintype "passive"))
      (node (ref "MOSFET4") (pin "7") (pinfunction "D_4_7") (pintype "passive"))
      (node (ref "MOSFET4") (pin "8") (pinfunction "D_8") (pintype "passive"))
      (node (ref "MOSFET4") (pin "9") (pinfunction "D_9") (pintype "passive"))
      (node (ref "R17") (pin "1") (pinfunction "1_1") (pintype "passive"))
      (node (ref "R31") (pin "1") (pinfunction "1_1") (pintype "passive"))
      (node (ref "VOUT1") (pin "TP") (pinfunction "P$1_TP") (pintype "bidirectional"))
    )
    (net (code "97") (name "VOUT-2") (class "Default")
      (node (ref "C7") (pin "1") (pinfunction "1_1") (pintype "passive"))
      (node (ref "CON1") (pin "P$1") (pinfunction "1_P$1") (pintype "bidirectional"))
      (node (ref "CON1") (pin "P$3") (pinfunction "3_P$3") (pintype "bidirectional"))
      (node (ref "CON2") (pin "P$1") (pinfunction "1_P$1") (pintype "bidirectional"))
      (node (ref "CON2") (pin "P$3") (pinfunction "3_P$3") (pintype "bidirectional"))
      (node (ref "CON3") (pin "P$1") (pinfunction "1_P$1") (pintype "bidirectional"))
      (node (ref "CON3") (pin "P$3") (pinfunction "3_P$3") (pintype "bidirectional"))
      (node (ref "CON4") (pin "P$1") (pinfunction "1_P$1") (pintype "bidirectional"))
      (node (ref "CON4") (pin "P$3") (pinfunction "3_P$3") (pintype "bidirectional"))
      (node (ref "IC13") (pin "2") (pinfunction "IN-_2") (pintype "bidirectional"))
      (node (ref "R17") (pin "2") (pinfunction "2_2") (pintype "passive"))
    )
    (net (code "98") (name "VOUT-USB") (class "Default")
      (node (ref "C5") (pin "1") (pinfunction "1_1") (pintype "passive"))
      (node (ref "C58") (pin "1") (pinfunction "1_1") (pintype "passive"))
      (node (ref "C6") (pin "1") (pinfunction "1_1") (pintype "passive"))
      (node (ref "IC1") (pin "11") (pinfunction "VDC_OUT_11") (pintype "output"))
      (node (ref "MOSFET2") (pin "5") (pinfunction "D_2_5") (pintype "passive"))
      (node (ref "MOSFET2") (pin "6") (pinfunction "D_3_6") (pintype "passive"))
      (node (ref "MOSFET2") (pin "7") (pinfunction "D_4_7") (pintype "passive"))
      (node (ref "MOSFET2") (pin "8") (pinfunction "D_8") (pintype "passive"))
      (node (ref "MOSFET2") (pin "9") (pinfunction "D_9") (pintype "passive"))
      (node (ref "MOSFET4") (pin "1") (pinfunction "S_2_1") (pintype "passive"))
      (node (ref "MOSFET4") (pin "2") (pinfunction "S_3_2") (pintype "passive"))
      (node (ref "MOSFET4") (pin "3") (pinfunction "S_3") (pintype "passive"))
      (node (ref "R48") (pin "1") (pinfunction "1_1") (pintype "passive"))
      (node (ref "VOUT") (pin "TP") (pinfunction "P$1_TP") (pintype "bidirectional"))
    )
    (net (code "99") (name "unconnected-(DISP-D3-Pad21)") (class "Default")
      (node (ref "DISP") (pin "21") (pinfunction "D3_21") (pintype "bidirectional"))
    )
    (net (code "100") (name "unconnected-(DISP-D4-Pad22)") (class "Default")
      (node (ref "DISP") (pin "22") (pinfunction "D4_22") (pintype "bidirectional"))
    )
    (net (code "101") (name "unconnected-(DISP-D5-Pad23)") (class "Default")
      (node (ref "DISP") (pin "23") (pinfunction "D5_23") (pintype "bidirectional"))
    )
    (net (code "102") (name "unconnected-(DISP-D6-Pad24)") (class "Default")
      (node (ref "DISP") (pin "24") (pinfunction "D6_24") (pintype "bidirectional"))
    )
    (net (code "103") (name "unconnected-(DISP-D7-Pad25)") (class "Default")
      (node (ref "DISP") (pin "25") (pinfunction "D7_25") (pintype "bidirectional"))
    )
    (net (code "104") (name "unconnected-(DISP-E{slash}RD-Pad17)") (class "Default")
      (node (ref "DISP") (pin "17") (pinfunction "E/RD_17") (pintype "input"))
    )
    (net (code "105") (name "unconnected-(DISP-IREF-Pad26)") (class "Default")
      (node (ref "DISP") (pin "26") (pinfunction "IREF_26") (pintype "input"))
    )
    (net (code "106") (name "unconnected-(DISP-NC-Pad7)") (class "Default")
      (node (ref "DISP") (pin "7") (pinfunction "NC_7") (pintype "no_connect"))
    )
    (net (code "107") (name "unconnected-(DISP-R{slash}W-Pad16)") (class "Default")
      (node (ref "DISP") (pin "16") (pinfunction "R/W_16") (pintype "input"))
    )
    (net (code "108") (name "unconnected-(IC1-D+-Pad17)") (class "Default")
      (node (ref "IC1") (pin "17") (pinfunction "D+_17") (pintype "bidirectional"))
    )
    (net (code "109") (name "unconnected-(IC1-D--Pad16)") (class "Default")
      (node (ref "IC1") (pin "16") (pinfunction "D-_16") (pintype "bidirectional"))
    )
    (net (code "110") (name "unconnected-(IC1-DNU1-Pad20)") (class "Default")
      (node (ref "IC1") (pin "20") (pinfunction "DNU1_20") (pintype "no_connect"))
    )
    (net (code "111") (name "unconnected-(IC1-DNU2-Pad21)") (class "Default")
      (node (ref "IC1") (pin "21") (pinfunction "DNU2_21") (pintype "no_connect"))
    )
    (net (code "112") (name "unconnected-(IC9-GPIO22-Pad34)") (class "Default")
      (node (ref "IC9") (pin "34") (pinfunction "GPIO22_34") (pintype "bidirectional"))
    )
    (net (code "113") (name "unconnected-(IC9-GPIO23-Pad35)") (class "Default")
      (node (ref "IC9") (pin "35") (pinfunction "GPIO23_35") (pintype "bidirectional"))
    )
    (net (code "114") (name "unconnected-(IC9-GPIO24-Pad36)") (class "Default")
      (node (ref "IC9") (pin "36") (pinfunction "GPIO24_36") (pintype "bidirectional"))
    )
    (net (code "115") (name "unconnected-(IC9-GPIO25-Pad37)") (class "Default")
      (node (ref "IC9") (pin "37") (pinfunction "GPIO25_37") (pintype "bidirectional"))
    )
    (net (code "116") (name "unconnected-(IC9-I2C0_SCL{slash}GPIO21-Pad33)") (class "Default")
      (node (ref "IC9") (pin "33") (pinfunction "I2C0_SCL/GPIO21_33") (pintype "bidirectional"))
    )
    (net (code "117") (name "unconnected-(IC9-I2C0_SDA{slash}GPIO20-Pad32)") (class "Default")
      (node (ref "IC9") (pin "32") (pinfunction "I2C0_SDA/GPIO20_32") (pintype "bidirectional"))
    )
    (net (code "118") (name "unconnected-(IC9-UART1_CTS{slash}I2C1_SDA{slash}SPI0_SCK{slash}GPIO6-Pad9)") (class "Default")
      (node (ref "IC9") (pin "9") (pinfunction "UART1_CTS/I2C1_SDA/SPI0_SCK/GPIO6_9") (pintype "bidirectional"))
    )
    (net (code "119") (name "unconnected-(IC9-UART1_CTS{slash}I2C1_SDA{slash}SPI1_SCK{slash}GPIO10-Pad14)") (class "Default")
      (node (ref "IC9") (pin "14") (pinfunction "UART1_CTS/I2C1_SDA/SPI1_SCK/GPIO10_14") (pintype "bidirectional"))
    )
    (net (code "120") (name "unconnected-(IC9-UART1_RTS{slash}I2C1_SCL{slash}SPI0_MOSI{slash}GPIO7-Pad10)") (class "Default")
      (node (ref "IC9") (pin "10") (pinfunction "UART1_RTS/I2C1_SCL/SPI0_MOSI/GPIO7_10") (pintype "bidirectional"))
    )
    (net (code "121") (name "unconnected-(USB1-SBU1-PadA8)") (class "Default")
      (node (ref "USB1") (pin "A8") (pinfunction "SBU1_A8") (pintype "bidirectional"))
    )
    (net (code "122") (name "unconnected-(USB1-SBU2-PadB8)") (class "Default")
      (node (ref "USB1") (pin "B8") (pinfunction "SBU2_B8") (pintype "bidirectional"))
    )
    (net (code "123") (name "~{BSY}") (class "Default")
      (node (ref "IC4") (pin "5") (pinfunction "RDY/~{BSY}_5") (pintype "bidirectional"))
      (node (ref "IC9") (pin "13") (pinfunction "UART1_RX/I2C0_SCL/SPI1_CS/GPIO9_13") (pintype "bidirectional"))
    )
    (net (code "124") (name "~{LDAC}") (class "Default")
      (node (ref "IC4") (pin "4") (pinfunction "~{LDAC}_4") (pintype "bidirectional"))
      (node (ref "IC9") (pin "12") (pinfunction "UART1_TX/I2C0_SDA/SPI1_MOSI/GPIO8_12") (pintype "bidirectional"))
    )
    (net (code "125") (name "~{QSPI_SS}") (class "Default")
      (node (ref "BOOT") (pin "TP") (pinfunction "P$1_TP") (pintype "bidirectional"))
      (node (ref "IC11") (pin "1") (pinfunction "~{CS}_1") (pintype "bidirectional"))
      (node (ref "IC9") (pin "60") (pinfunction "QSPI_SS_60") (pintype "bidirectional"))
      (node (ref "R18") (pin "1") (pinfunction "1_1") (pintype "passive"))
    )
  )
)
